# IRIS1304_v3_0.net
KiCad netlist of a schematic drawn in EAGLE
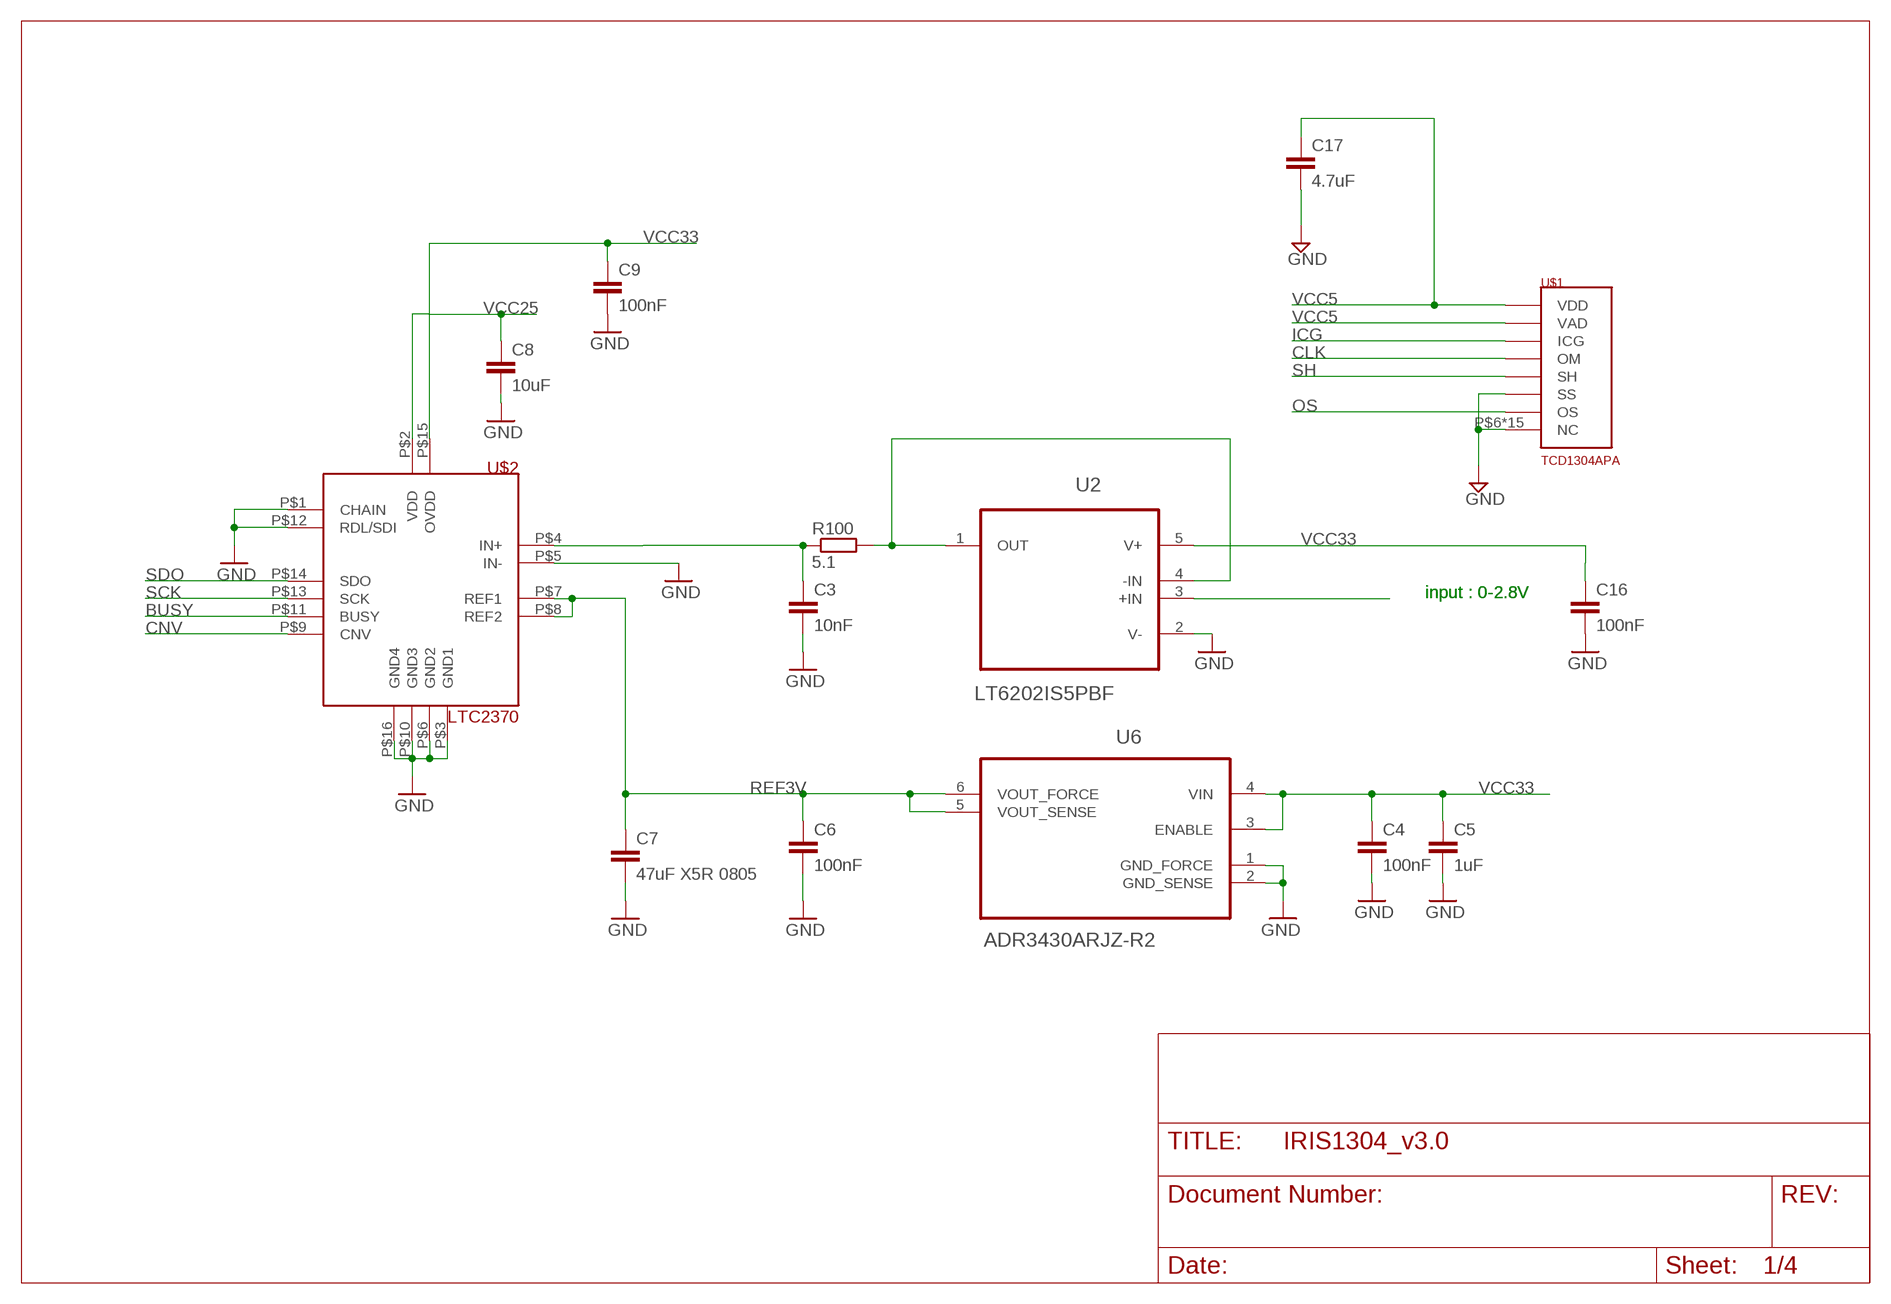
[diagram p0: schematic, sheet 1]
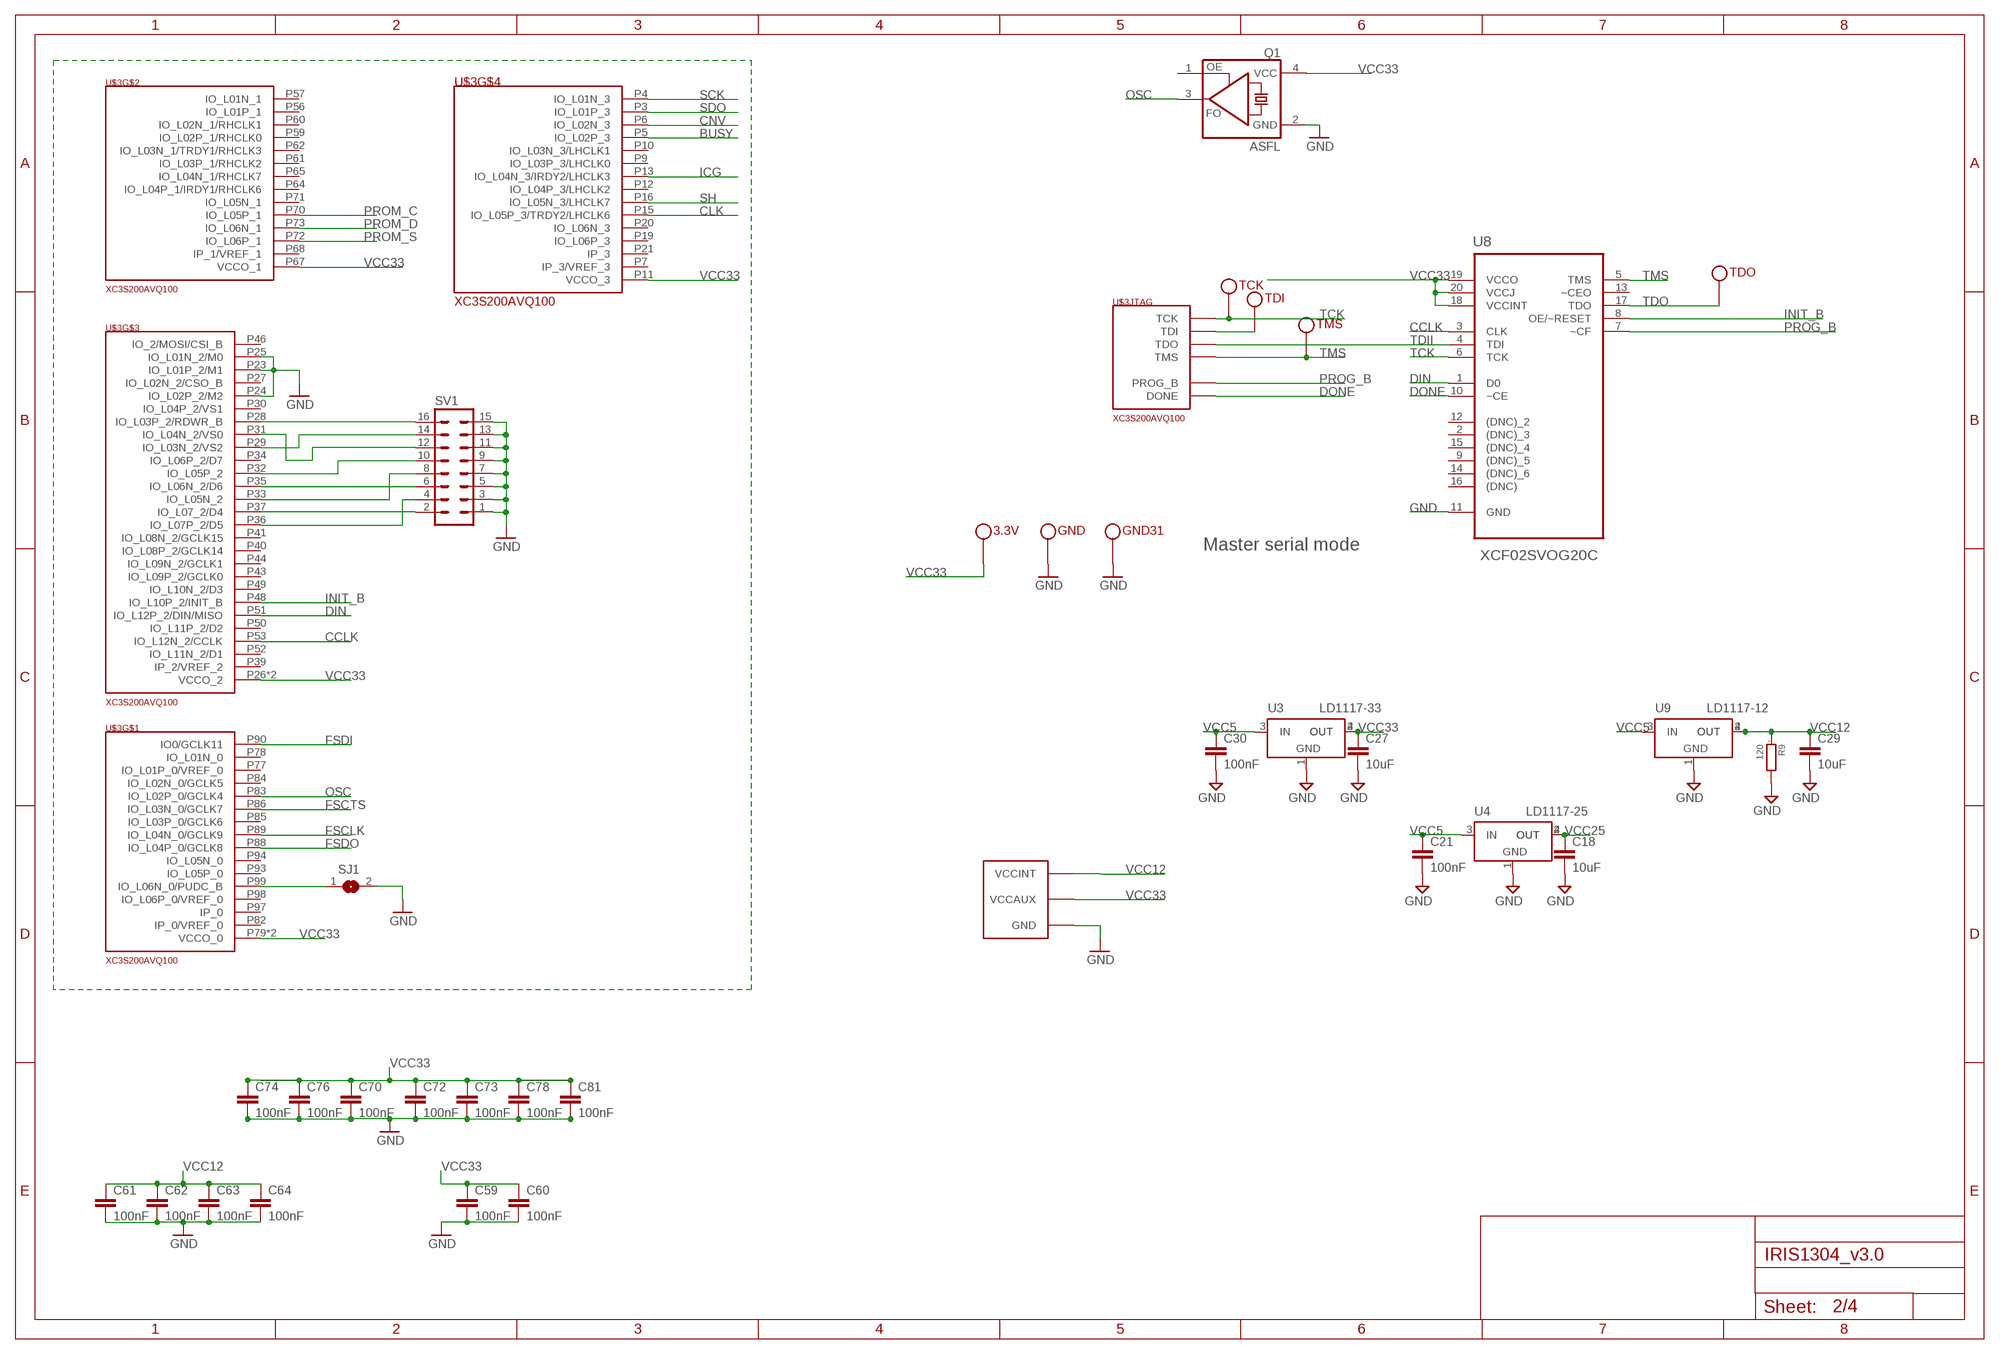
[diagram p1: schematic, sheet 2]
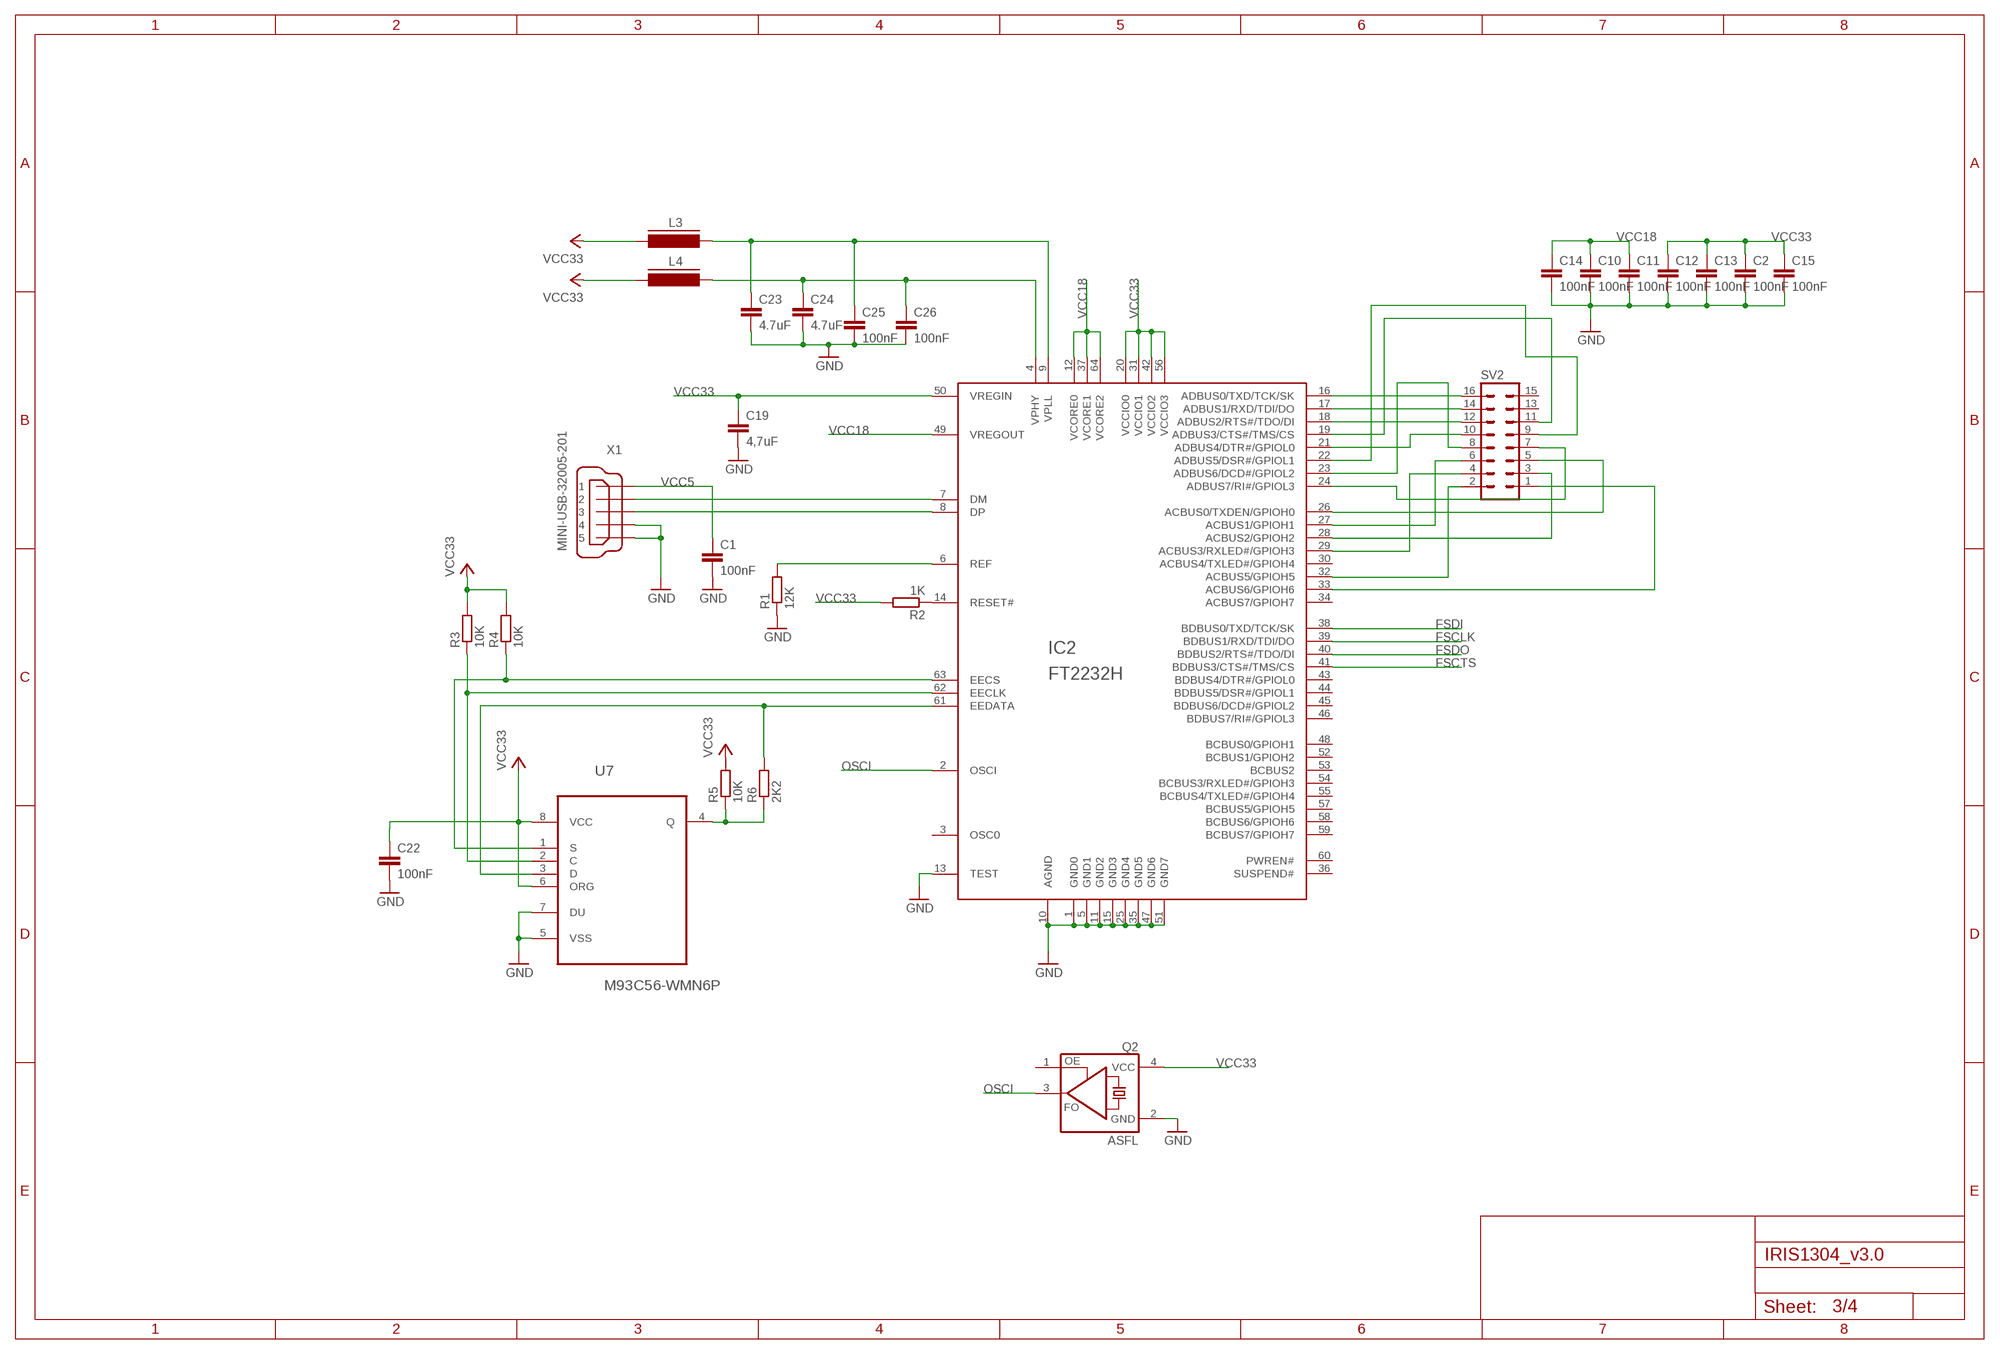
[diagram p2: schematic, sheet 3]
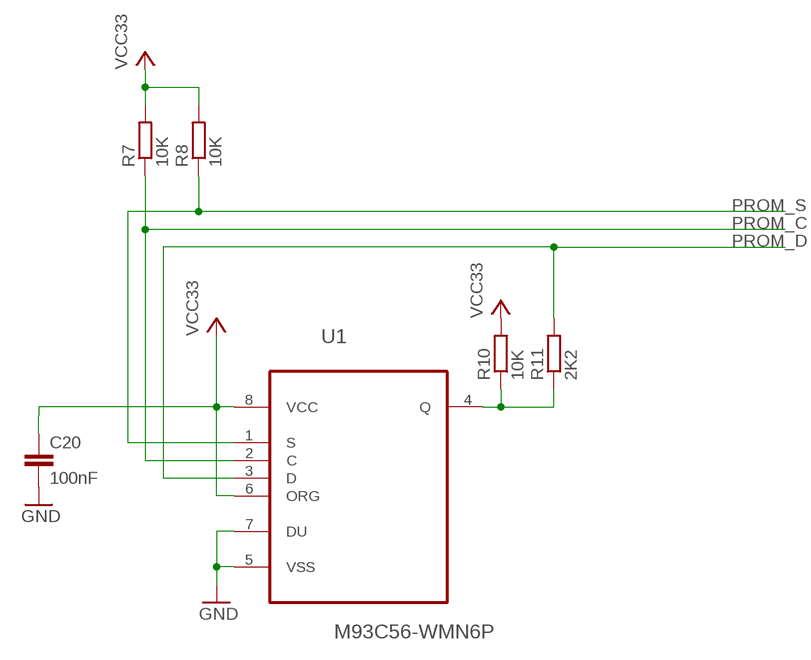
[diagram p3: schematic, sheet 4]

(export (version "E")
  (design (tool "Eeschema 10.0.6"))
  (components
    (comp (ref "C1")
      (value "100nF")
      (footprint "eagle-import:C0603")
      (fields (field (name "MF") "AVX") (field (name "MPN") "06033G104ZAT2A"))
      (libsource (lib "eagle-import") (part "C-EUC0603"))
    )
    (comp (ref "C2")
      (value "100nF")
      (footprint "eagle-import:C0603")
      (fields (field (name "MF") "AVX") (field (name "MPN") "06033G104ZAT2A"))
      (libsource (lib "eagle-import") (part "C-EUC0603"))
    )
    (comp (ref "C10")
      (value "100nF")
      (footprint "eagle-import:C0603")
      (fields (field (name "MF") "AVX") (field (name "MPN") "06033G104ZAT2A"))
      (libsource (lib "eagle-import") (part "C-EUC0603"))
    )
    (comp (ref "C11")
      (value "100nF")
      (footprint "eagle-import:C0603")
      (fields (field (name "MF") "AVX") (field (name "MPN") "06033G104ZAT2A"))
      (libsource (lib "eagle-import") (part "C-EUC0603"))
    )
    (comp (ref "C12")
      (value "100nF")
      (footprint "eagle-import:C0603")
      (fields (field (name "MF") "AVX") (field (name "MPN") "06033G104ZAT2A"))
      (libsource (lib "eagle-import") (part "C-EUC0603"))
    )
    (comp (ref "C13")
      (value "100nF")
      (footprint "eagle-import:C0603")
      (fields (field (name "MF") "AVX") (field (name "MPN") "06033G104ZAT2A"))
      (libsource (lib "eagle-import") (part "C-EUC0603"))
    )
    (comp (ref "C14")
      (value "100nF")
      (footprint "eagle-import:C0603")
      (fields (field (name "MF") "AVX") (field (name "MPN") "06033G104ZAT2A"))
      (libsource (lib "eagle-import") (part "C-EUC0603"))
    )
    (comp (ref "C15")
      (value "100nF")
      (footprint "eagle-import:C0603")
      (fields (field (name "MF") "AVX") (field (name "MPN") "06033G104ZAT2A"))
      (libsource (lib "eagle-import") (part "C-EUC0603"))
    )
    (comp (ref "C19")
      (value "4,7uF")
      (footprint "eagle-import:C0805")
      (fields (field (name "MF") "AVX") (field (name "MPN") "0805ZD335KAT2A"))
      (libsource (lib "eagle-import") (part "C-EUC0805"))
    )
    (comp (ref "C22")
      (value "100nF")
      (footprint "eagle-import:C0603")
      (fields (field (name "MF") "AVX") (field (name "MPN") "06033G104ZAT2A"))
      (libsource (lib "eagle-import") (part "C-EUC0603"))
    )
    (comp (ref "C23")
      (value "4.7uF")
      (footprint "eagle-import:C0603")
      (fields (field (name "MF") "YAGEO (PHYCOMP)") (field (name "MPN") "CC0603KRX5R6BB475"))
      (libsource (lib "eagle-import") (part "C-EUC0603"))
    )
    (comp (ref "C24")
      (value "4.7uF")
      (footprint "eagle-import:C0603")
      (fields (field (name "MF") "YAGEO (PHYCOMP)") (field (name "MPN") "CC0603KRX5R6BB475"))
      (libsource (lib "eagle-import") (part "C-EUC0603"))
    )
    (comp (ref "C25")
      (value "100nF")
      (footprint "eagle-import:C0603")
      (fields (field (name "MF") "AVX") (field (name "MPN") "06033G104ZAT2A"))
      (libsource (lib "eagle-import") (part "C-EUC0603"))
    )
    (comp (ref "C26")
      (value "100nF")
      (footprint "eagle-import:C0603")
      (fields (field (name "MF") "AVX") (field (name "MPN") "06033G104ZAT2A"))
      (libsource (lib "eagle-import") (part "C-EUC0603"))
    )
    (comp (ref "IC2")
      (value "FT2232H")
      (footprint "eagle-import:LQFP64")
      (fields (field (name "MF") "FTDI") (field (name "MPN") "FT2232HL-R"))
      (libsource (lib "eagle-import") (part "FT2232H"))
    )
    (comp (ref "L3")
      (value "FERRITE_BEAD805")
      (footprint "eagle-import:FB805")
      (libsource (lib "eagle-import") (part "FERRITE_BEAD805"))
    )
    (comp (ref "L4")
      (value "FERRITE_BEAD805")
      (footprint "eagle-import:FB805")
      (libsource (lib "eagle-import") (part "FERRITE_BEAD805"))
    )
    (comp (ref "Q2")
      (value "ASFL")
      (footprint "eagle-import:ASF")
      (fields
        (field (name "MPN") "ASFLM1-50.000MHZ-C-T")
        (field (name "MF") "ABRACON")
        (field (name "MPN_1") "ASFL1-12.000MHZ-EK-T")
        (field (name "OC_FARNELL") "7943088")
      )
      (libsource (lib "eagle-import") (part "ASFL"))
    )
    (comp (ref "R1")
      (value "12K")
      (footprint "eagle-import:R0603")
      (fields (field (name "MF") "TE CONNECTIVITY") (field (name "MPN") "CPF0201D12K1C1"))
      (libsource (lib "eagle-import") (part "R-EU_R0603"))
    )
    (comp (ref "R2")
      (value "1K")
      (footprint "eagle-import:R0603")
      (fields (field (name "MF") "VISHAY DRALORIC") (field (name "MPN") "CRCW06031K00FKEA"))
      (libsource (lib "eagle-import") (part "R-EU_R0603"))
    )
    (comp (ref "R3")
      (value "10K")
      (footprint "eagle-import:R0603")
      (fields (field (name "MF") "TE CONNECTIVITY / NEOHM") (field (name "MPN") "CPF0603F10KC1"))
      (libsource (lib "eagle-import") (part "R-EU_R0603"))
    )
    (comp (ref "R4")
      (value "10K")
      (footprint "eagle-import:R0603")
      (fields (field (name "MF") "TE CONNECTIVITY / NEOHM") (field (name "MPN") "CPF0603F10KC1"))
      (libsource (lib "eagle-import") (part "R-EU_R0603"))
    )
    (comp (ref "R5")
      (value "10K")
      (footprint "eagle-import:R0603")
      (fields (field (name "MF") "TE CONNECTIVITY / NEOHM") (field (name "MPN") "CPF0603F10KC1"))
      (libsource (lib "eagle-import") (part "R-EU_R0603"))
    )
    (comp (ref "R6")
      (value "2K2")
      (footprint "eagle-import:R0603")
      (fields (field (name "MF") "PANASONIC ELECTRONIC COMPONENTS") (field (name "MPN") "ERJP03F2201V"))
      (libsource (lib "eagle-import") (part "R-EU_R0603"))
    )
    (comp (ref "SV2")
      (value "ML16")
      (footprint "eagle-import:ML16")
      (libsource (lib "eagle-import") (part "ML16"))
    )
    (comp (ref "U7")
      (value "M93C56-WMN6P")
      (footprint "eagle-import:SOIC127P600X175-8N")
      (fields (field (name "MF") "STMICROELECTRONICS"))
      (libsource (lib "eagle-import") (part "M93C56-WMN6P"))
    )
    (comp (ref "X1")
      (value "MINI-USB-32005-201")
      (footprint "eagle-import:32005-201")
      (fields
        (field (name "MF") "WURTH ELEKTRONIK")
        (field (name "MPN") "65100516121")
        (field (name "OC_FARNELL") "1642036")
      )
      (libsource (lib "eagle-import") (part "MINI-USB-32005-201"))
    )
    (comp (ref "C20")
      (value "100nF")
      (footprint "eagle-import:C0603")
      (fields (field (name "MF") "AVX") (field (name "MPN") "06033G104ZAT2A"))
      (libsource (lib "eagle-import") (part "C-EUC0603"))
    )
    (comp (ref "R7")
      (value "10K")
      (footprint "eagle-import:R0603")
      (fields (field (name "MF") "TE CONNECTIVITY / NEOHM") (field (name "MPN") "CPF0603F10KC1"))
      (libsource (lib "eagle-import") (part "R-EU_R0603"))
    )
    (comp (ref "R8")
      (value "10K")
      (footprint "eagle-import:R0603")
      (fields (field (name "MF") "TE CONNECTIVITY / NEOHM") (field (name "MPN") "CPF0603F10KC1"))
      (libsource (lib "eagle-import") (part "R-EU_R0603"))
    )
    (comp (ref "R10")
      (value "10K")
      (footprint "eagle-import:R0603")
      (fields (field (name "MF") "TE CONNECTIVITY / NEOHM") (field (name "MPN") "CPF0603F10KC1"))
      (libsource (lib "eagle-import") (part "R-EU_R0603"))
    )
    (comp (ref "R11")
      (value "2K2")
      (footprint "eagle-import:R0603")
      (fields (field (name "MF") "PANASONIC ELECTRONIC COMPONENTS") (field (name "MPN") "ERJP03F2201V"))
      (libsource (lib "eagle-import") (part "R-EU_R0603"))
    )
    (comp (ref "U1")
      (value "M93C56-WMN6P")
      (footprint "eagle-import:SOIC127P600X175-8N")
      (fields (field (name "MF") "STMICROELECTRONICS"))
      (libsource (lib "eagle-import") (part "M93C56-WMN6P"))
    )
    (comp (ref "3.3V")
      (value "TEST")
      (footprint "eagle-import:TEST")
      (fields (field (name "MF") "ITT CANNON") (field (name "MPN") "001-1007-040FB9"))
      (libsource (lib "eagle-import") (part "TEST"))
    )
    (comp (ref "C18")
      (value "10uF")
      (footprint "eagle-import:C0603")
      (fields (field (name "MF") "KEMET") (field (name "MPN") "C0603C106M9PACTU"))
      (libsource (lib "eagle-import") (part "C-EUC0603"))
    )
    (comp (ref "C21")
      (value "100nF")
      (footprint "eagle-import:C0603")
      (fields (field (name "MF") "AVX") (field (name "MPN") "06033G104ZAT2A"))
      (libsource (lib "eagle-import") (part "C-EUC0603"))
    )
    (comp (ref "C27")
      (value "10uF")
      (footprint "eagle-import:C0603")
      (fields (field (name "MF") "KEMET") (field (name "MPN") "C0603C106M9PACTU"))
      (libsource (lib "eagle-import") (part "C-EUC0603"))
    )
    (comp (ref "C29")
      (value "10uF")
      (footprint "eagle-import:C0603")
      (fields (field (name "MF") "KEMET") (field (name "MPN") "C0603C106M9PACTU"))
      (libsource (lib "eagle-import") (part "C-EUC0603"))
    )
    (comp (ref "C30")
      (value "100nF")
      (footprint "eagle-import:C0603")
      (fields (field (name "MF") "AVX") (field (name "MPN") "06033G104ZAT2A"))
      (libsource (lib "eagle-import") (part "C-EUC0603"))
    )
    (comp (ref "C59")
      (value "100nF")
      (footprint "eagle-import:C0603")
      (fields (field (name "MF") "AVX") (field (name "MPN") "06033G104ZAT2A"))
      (libsource (lib "eagle-import") (part "C-EUC0603"))
    )
    (comp (ref "C60")
      (value "100nF")
      (footprint "eagle-import:C0603")
      (fields (field (name "MF") "AVX") (field (name "MPN") "06033G104ZAT2A"))
      (libsource (lib "eagle-import") (part "C-EUC0603"))
    )
    (comp (ref "C61")
      (value "100nF")
      (footprint "eagle-import:C0603")
      (fields (field (name "MF") "AVX") (field (name "MPN") "06033G104ZAT2A"))
      (libsource (lib "eagle-import") (part "C-EUC0603"))
    )
    (comp (ref "C62")
      (value "100nF")
      (footprint "eagle-import:C0603")
      (fields (field (name "MF") "AVX") (field (name "MPN") "06033G104ZAT2A"))
      (libsource (lib "eagle-import") (part "C-EUC0603"))
    )
    (comp (ref "C63")
      (value "100nF")
      (footprint "eagle-import:C0603")
      (fields (field (name "MF") "AVX") (field (name "MPN") "06033G104ZAT2A"))
      (libsource (lib "eagle-import") (part "C-EUC0603"))
    )
    (comp (ref "C64")
      (value "100nF")
      (footprint "eagle-import:C0603")
      (fields (field (name "MF") "AVX") (field (name "MPN") "06033G104ZAT2A"))
      (libsource (lib "eagle-import") (part "C-EUC0603"))
    )
    (comp (ref "C70")
      (value "100nF")
      (footprint "eagle-import:C0603")
      (fields (field (name "MF") "AVX") (field (name "MPN") "06033G104ZAT2A"))
      (libsource (lib "eagle-import") (part "C-EUC0603"))
    )
    (comp (ref "C72")
      (value "100nF")
      (footprint "eagle-import:C0603")
      (fields (field (name "MF") "AVX") (field (name "MPN") "06033G104ZAT2A"))
      (libsource (lib "eagle-import") (part "C-EUC0603"))
    )
    (comp (ref "C73")
      (value "100nF")
      (footprint "eagle-import:C0603")
      (fields (field (name "MF") "AVX") (field (name "MPN") "06033G104ZAT2A"))
      (libsource (lib "eagle-import") (part "C-EUC0603"))
    )
    (comp (ref "C74")
      (value "100nF")
      (footprint "eagle-import:C0603")
      (fields (field (name "MF") "AVX") (field (name "MPN") "06033G104ZAT2A"))
      (libsource (lib "eagle-import") (part "C-EUC0603"))
    )
    (comp (ref "C76")
      (value "100nF")
      (footprint "eagle-import:C0603")
      (fields (field (name "MF") "AVX") (field (name "MPN") "06033G104ZAT2A"))
      (libsource (lib "eagle-import") (part "C-EUC0603"))
    )
    (comp (ref "C78")
      (value "100nF")
      (footprint "eagle-import:C0603")
      (fields (field (name "MF") "AVX") (field (name "MPN") "06033G104ZAT2A"))
      (libsource (lib "eagle-import") (part "C-EUC0603"))
    )
    (comp (ref "C81")
      (value "100nF")
      (footprint "eagle-import:C0603")
      (fields (field (name "MF") "AVX") (field (name "MPN") "06033G104ZAT2A"))
      (libsource (lib "eagle-import") (part "C-EUC0603"))
    )
    (comp (ref "GND")
      (value "TEST")
      (footprint "eagle-import:TEST")
      (fields (field (name "MF") "ITT CANNON") (field (name "MPN") "001-1007-040FB9"))
      (libsource (lib "eagle-import") (part "TEST"))
    )
    (comp (ref "GND31")
      (value "TEST")
      (footprint "eagle-import:TEST")
      (fields (field (name "MF") "ITT CANNON") (field (name "MPN") "001-1007-040FB9"))
      (libsource (lib "eagle-import") (part "TEST"))
    )
    (comp (ref "Q1")
      (value "ASFL")
      (footprint "eagle-import:ASF")
      (fields
        (field (name "MPN") "ASFLM1-50.000MHZ-C-T")
        (field (name "MF") "ABRACON")
        (field (name "MPN_1") "ASFL1-12.000MHZ-EK-T")
        (field (name "OC_FARNELL") "7943088")
      )
      (libsource (lib "eagle-import") (part "ASFL"))
    )
    (comp (ref "R9")
      (value "120")
      (footprint "eagle-import:0805@1")
      (fields (field (name "MF") "TE CONNECTIVITY / SIGMA INDUCTORS") (field (name "MPN") "BMB2A0120AN1"))
      (libsource (lib "eagle-import") (part "R0805"))
    )
    (comp (ref "SJ1") (value "SJ") (footprint "eagle-import:SJ") (libsource (lib "eagle-import") (part "SJ")))
    (comp (ref "SV1")
      (value "ML16")
      (footprint "eagle-import:ML16")
      (libsource (lib "eagle-import") (part "ML16"))
    )
    (comp (ref "TCK")
      (value "TEST")
      (footprint "eagle-import:TEST")
      (fields (field (name "MF") "ITT CANNON") (field (name "MPN") "001-1007-040FB9"))
      (libsource (lib "eagle-import") (part "TEST"))
    )
    (comp (ref "TDI")
      (value "TEST")
      (footprint "eagle-import:TEST")
      (fields (field (name "MF") "ITT CANNON") (field (name "MPN") "001-1007-040FB9"))
      (libsource (lib "eagle-import") (part "TEST"))
    )
    (comp (ref "TDO")
      (value "TEST")
      (footprint "eagle-import:TEST")
      (fields (field (name "MF") "ITT CANNON") (field (name "MPN") "001-1007-040FB9"))
      (libsource (lib "eagle-import") (part "TEST"))
    )
    (comp (ref "TMS")
      (value "TEST")
      (footprint "eagle-import:TEST")
      (fields (field (name "MF") "ITT CANNON") (field (name "MPN") "001-1007-040FB9"))
      (libsource (lib "eagle-import") (part "TEST"))
    )
    (comp (ref "U$3")
      (value "XC3S200AVQ100")
      (footprint "eagle-import:VQ100")
      (fields
        (field (name "MF") "XILINX")
        (field (name "MPN") "XC3S200A-4VQG100C")
        (field (name "OC_FARNELL") "1876204")
      )
      (libsource (lib "eagle-import") (part "XC3S200AVQ100"))
    )
    (comp (ref "U3")
      (value "LD1117-33")
      (footprint "eagle-import:SOT223")
      (fields (field (name "MF") "LINEAR TECHNOLOGY") (field (name "MPN") "LT1117CST-3.3#PBF"))
      (libsource (lib "eagle-import") (part "LD1117"))
    )
    (comp (ref "U4")
      (value "LD1117-25")
      (footprint "eagle-import:SOT223")
      (fields (field (name "MF") "STMICROELECTRONICS") (field (name "MPN") "LD1117S25TR"))
      (libsource (lib "eagle-import") (part "LD1117"))
    )
    (comp (ref "U8")
      (value "XCF02SVOG20C")
      (footprint "eagle-import:SOP65P640X119-20N")
      (fields (field (name "MF") "XILINX"))
      (libsource (lib "eagle-import") (part "XCF02SVOG20C"))
    )
    (comp (ref "U9")
      (value "LD1117-12")
      (footprint "eagle-import:SOT223")
      (fields (field (name "MF") "LINEAR TECHNOLOGY") (field (name "MPN") "LT1117IST#PBF"))
      (libsource (lib "eagle-import") (part "LD1117"))
    )
    (comp (ref "C3")
      (value "10nF")
      (footprint "eagle-import:C0603")
      (fields (field (name "MF") "AVX") (field (name "MPN") "06035G103ZAT2A"))
      (libsource (lib "eagle-import") (part "C-EUC0603"))
    )
    (comp (ref "C4")
      (value "100nF")
      (footprint "eagle-import:C0603")
      (fields (field (name "MF") "AVX") (field (name "MPN") "06033G104ZAT2A"))
      (libsource (lib "eagle-import") (part "C-EUC0603"))
    )
    (comp (ref "C5")
      (value "1uF")
      (footprint "eagle-import:C0603")
      (fields (field (name "MF") "KEMET") (field (name "MPN") "C0603C105K3PACTU"))
      (libsource (lib "eagle-import") (part "C-EUC0603"))
    )
    (comp (ref "C6")
      (value "100nF")
      (footprint "eagle-import:C0603")
      (fields (field (name "MF") "AVX") (field (name "MPN") "06033G104ZAT2A"))
      (libsource (lib "eagle-import") (part "C-EUC0603"))
    )
    (comp (ref "C7")
      (value "47uF X5R 0805")
      (footprint "eagle-import:C0805")
      (fields (field (name "MF") "KEMET") (field (name "MPN") "C0805C476M9PACTU"))
      (libsource (lib "eagle-import") (part "C-EUC0805"))
    )
    (comp (ref "C8")
      (value "10uF")
      (footprint "eagle-import:C0603")
      (fields (field (name "MF") "KEMET") (field (name "MPN") "C0603C106M9PACTU"))
      (libsource (lib "eagle-import") (part "C-EUC0603"))
    )
    (comp (ref "C9")
      (value "100nF")
      (footprint "eagle-import:C0603")
      (fields (field (name "MF") "AVX") (field (name "MPN") "06033G104ZAT2A"))
      (libsource (lib "eagle-import") (part "C-EUC0603"))
    )
    (comp (ref "C16")
      (value "100nF")
      (footprint "eagle-import:C0603")
      (fields (field (name "MF") "AVX") (field (name "MPN") "06033G104ZAT2A"))
      (libsource (lib "eagle-import") (part "C-EUC0603"))
    )
    (comp (ref "C17")
      (value "4.7uF")
      (footprint "eagle-import:C0603")
      (fields (field (name "MF") "YAGEO (PHYCOMP)") (field (name "MPN") "CC0603KRX5R6BB475"))
      (libsource (lib "eagle-import") (part "C-EUC0603"))
    )
    (comp (ref "R100")
      (value "5.1")
      (footprint "eagle-import:R0603")
      (fields (field (name "MF") "VISHAY DALE") (field (name "MPN") "CRCW06035R10FNEA"))
      (libsource (lib "eagle-import") (part "R-EU_R0603"))
    )
    (comp (ref "U$1")
      (value "TCD1304APA")
      (footprint "eagle-import:ILX511")
      (libsource (lib "eagle-import") (part "TCD1304APA"))
    )
    (comp (ref "U$2")
      (value "LTC2370")
      (footprint "eagle-import:MSOP-16")
      (fields (field (name "MF") "LINEAR TECHNOLOGY") (field (name "MPN") "LTC2370CMS-16"))
      (libsource (lib "eagle-import") (part "LTC2370"))
    )
    (comp (ref "U2")
      (value "LT6202IS5PBF")
      (footprint "eagle-import:SOT95P280X100-5N")
      (fields (field (name "MPN") "LT6202IS5#PBF") (field (name "MF") "LINEAR TECHNOLOGY"))
      (libsource (lib "eagle-import") (part "LT6202IS5PBF"))
    )
    (comp (ref "U6")
      (value "ADR3430ARJZ-R2")
      (footprint "eagle-import:SOT95P280X145-6N")
      (fields (field (name "MF") "ANALOG DEVICES"))
      (libsource (lib "eagle-import") (part "ADR3430ARJZ-R2"))
    )
  )
  (nets
    (net (code "1") (name "BUSY") (class "Default")
      (node (ref "U$2") (pin "P$11") (pinfunction "BUSY_P$11") (pintype "bidirectional"))
      (node (ref "U$3") (pin "P5") (pinfunction "IO_L02P_3_P5") (pintype "bidirectional"))
    )
    (net (code "2") (name "CCLK") (class "Default")
      (node (ref "U$3") (pin "P53") (pinfunction "IO_L12N_2/CCLK_P53") (pintype "bidirectional"))
      (node (ref "U8") (pin "3") (pinfunction "CLK_3") (pintype "input"))
    )
    (net (code "3") (name "CLK") (class "Default")
      (node (ref "U$1") (pin "P$4") (pinfunction "OM_P$4") (pintype "bidirectional"))
      (node (ref "U$3") (pin "P15") (pinfunction "IO_L05P_3/TRDY2/LHCLK6_P15") (pintype "bidirectional"))
    )
    (net (code "4") (name "CNV") (class "Default")
      (node (ref "U$2") (pin "P$9") (pinfunction "CNV_P$9") (pintype "bidirectional"))
      (node (ref "U$3") (pin "P6") (pinfunction "IO_L02N_3_P6") (pintype "bidirectional"))
    )
    (net (code "5") (name "DIN") (class "Default")
      (node (ref "U$3") (pin "P51") (pinfunction "IO_L12P_2/DIN/MISO_P51") (pintype "bidirectional"))
      (node (ref "U8") (pin "1") (pinfunction "D0_1") (pintype "input"))
    )
    (net (code "6") (name "DONE") (class "Default")
      (node (ref "U$3") (pin "P54") (pinfunction "DONE_P54") (pintype "bidirectional"))
      (node (ref "U8") (pin "10") (pinfunction "~{CE}_10") (pintype "input"))
    )
    (net (code "7") (name "FSCLK") (class "Default")
      (node (ref "IC2") (pin "39") (pinfunction "BDBUS1/RXD/TDI/DO_39") (pintype "bidirectional"))
      (node (ref "U$3") (pin "P89") (pinfunction "IO_L04N_0/GCLK9_P89") (pintype "bidirectional"))
    )
    (net (code "8") (name "FSCTS") (class "Default")
      (node (ref "IC2") (pin "41") (pinfunction "BDBUS3/CTS#/TMS/CS_41") (pintype "bidirectional"))
      (node (ref "U$3") (pin "P86") (pinfunction "IO_L03N_0/GCLK7_P86") (pintype "bidirectional"))
    )
    (net (code "9") (name "FSDI") (class "Default")
      (node (ref "IC2") (pin "38") (pinfunction "BDBUS0/TXD/TCK/SK_38") (pintype "bidirectional"))
      (node (ref "U$3") (pin "P90") (pinfunction "IO0/GCLK11_P90") (pintype "bidirectional"))
    )
    (net (code "10") (name "FSDO") (class "Default")
      (node (ref "IC2") (pin "40") (pinfunction "BDBUS2/RTS#/TDO/DI_40") (pintype "bidirectional"))
      (node (ref "U$3") (pin "P88") (pinfunction "IO_L04P_0/GCLK8_P88") (pintype "bidirectional"))
    )
    (net (code "11") (name "GND") (class "Default")
      (node (ref "C1") (pin "2") (pinfunction "2_2") (pintype "passive"))
      (node (ref "C10") (pin "2") (pinfunction "2_2") (pintype "passive"))
      (node (ref "C11") (pin "2") (pinfunction "2_2") (pintype "passive"))
      (node (ref "C12") (pin "2") (pinfunction "2_2") (pintype "passive"))
      (node (ref "C13") (pin "2") (pinfunction "2_2") (pintype "passive"))
      (node (ref "C14") (pin "2") (pinfunction "2_2") (pintype "passive"))
      (node (ref "C15") (pin "2") (pinfunction "2_2") (pintype "passive"))
      (node (ref "C16") (pin "2") (pinfunction "2_2") (pintype "passive"))
      (node (ref "C17") (pin "2") (pinfunction "2_2") (pintype "passive"))
      (node (ref "C18") (pin "2") (pinfunction "2_2") (pintype "passive"))
      (node (ref "C19") (pin "2") (pinfunction "2_2") (pintype "passive"))
      (node (ref "C2") (pin "2") (pinfunction "2_2") (pintype "passive"))
      (node (ref "C20") (pin "2") (pinfunction "2_2") (pintype "passive"))
      (node (ref "C21") (pin "2") (pinfunction "2_2") (pintype "passive"))
      (node (ref "C22") (pin "2") (pinfunction "2_2") (pintype "passive"))
      (node (ref "C23") (pin "2") (pinfunction "2_2") (pintype "passive"))
      (node (ref "C24") (pin "2") (pinfunction "2_2") (pintype "passive"))
      (node (ref "C25") (pin "2") (pinfunction "2_2") (pintype "passive"))
      (node (ref "C26") (pin "2") (pinfunction "2_2") (pintype "passive"))
      (node (ref "C27") (pin "2") (pinfunction "2_2") (pintype "passive"))
      (node (ref "C29") (pin "2") (pinfunction "2_2") (pintype "passive"))
      (node (ref "C3") (pin "2") (pinfunction "2_2") (pintype "passive"))
      (node (ref "C30") (pin "2") (pinfunction "2_2") (pintype "passive"))
      (node (ref "C4") (pin "2") (pinfunction "2_2") (pintype "passive"))
      (node (ref "C5") (pin "2") (pinfunction "2_2") (pintype "passive"))
      (node (ref "C59") (pin "2") (pinfunction "2_2") (pintype "passive"))
      (node (ref "C6") (pin "2") (pinfunction "2_2") (pintype "passive"))
      (node (ref "C60") (pin "2") (pinfunction "2_2") (pintype "passive"))
      (node (ref "C61") (pin "2") (pinfunction "2_2") (pintype "passive"))
      (node (ref "C62") (pin "2") (pinfunction "2_2") (pintype "passive"))
      (node (ref "C63") (pin "2") (pinfunction "2_2") (pintype "passive"))
      (node (ref "C64") (pin "2") (pinfunction "2_2") (pintype "passive"))
      (node (ref "C7") (pin "2") (pinfunction "2_2") (pintype "passive"))
      (node (ref "C70") (pin "2") (pinfunction "2_2") (pintype "passive"))
      (node (ref "C72") (pin "2") (pinfunction "2_2") (pintype "passive"))
      (node (ref "C73") (pin "2") (pinfunction "2_2") (pintype "passive"))
      (node (ref "C74") (pin "2") (pinfunction "2_2") (pintype "passive"))
      (node (ref "C76") (pin "2") (pinfunction "2_2") (pintype "passive"))
      (node (ref "C78") (pin "2") (pinfunction "2_2") (pintype "passive"))
      (node (ref "C8") (pin "2") (pinfunction "2_2") (pintype "passive"))
      (node (ref "C81") (pin "2") (pinfunction "2_2") (pintype "passive"))
      (node (ref "C9") (pin "2") (pinfunction "2_2") (pintype "passive"))
      (node (ref "GND") (pin "P$1") (pinfunction "P$1_P$1") (pintype "bidirectional"))
      (node (ref "GND31") (pin "P$1") (pinfunction "P$1_P$1") (pintype "bidirectional"))
      (node (ref "IC2") (pin "1") (pinfunction "GND0_1") (pintype "bidirectional"))
      (node (ref "IC2") (pin "10") (pinfunction "AGND_10") (pintype "bidirectional"))
      (node (ref "IC2") (pin "11") (pinfunction "GND2_11") (pintype "bidirectional"))
      (node (ref "IC2") (pin "13") (pinfunction "TEST_13") (pintype "bidirectional"))
      (node (ref "IC2") (pin "15") (pinfunction "GND3_15") (pintype "bidirectional"))
      (node (ref "IC2") (pin "25") (pinfunction "GND4_25") (pintype "bidirectional"))
      (node (ref "IC2") (pin "35") (pinfunction "GND5_35") (pintype "bidirectional"))
      (node (ref "IC2") (pin "47") (pinfunction "GND6_47") (pintype "bidirectional"))
      (node (ref "IC2") (pin "5") (pinfunction "GND1_5") (pintype "bidirectional"))
      (node (ref "IC2") (pin "51") (pinfunction "GND7_51") (pintype "bidirectional"))
      (node (ref "Q1") (pin "2") (pinfunction "GND_2") (pintype "power_in"))
      (node (ref "Q2") (pin "2") (pinfunction "GND_2") (pintype "power_in"))
      (node (ref "R1") (pin "1") (pinfunction "1_1") (pintype "passive"))
      (node (ref "R9") (pin "2") (pinfunction "2_2") (pintype "passive"))
      (node (ref "SJ1") (pin "2") (pinfunction "2_2") (pintype "passive"))
      (node (ref "SV1") (pin "1") (pinfunction "1_1") (pintype "passive"))
      (node (ref "SV1") (pin "11") (pinfunction "11_11") (pintype "passive"))
      (node (ref "SV1") (pin "13") (pinfunction "13_13") (pintype "passive"))
      (node (ref "SV1") (pin "15") (pinfunction "15_15") (pintype "passive"))
      (node (ref "SV1") (pin "3") (pinfunction "3_3") (pintype "passive"))
      (node (ref "SV1") (pin "5") (pinfunction "5_5") (pintype "passive"))
      (node (ref "SV1") (pin "7") (pinfunction "7_7") (pintype "passive"))
      (node (ref "SV1") (pin "9") (pinfunction "9_9") (pintype "passive"))
      (node (ref "U$1") (pin "P$10") (pinfunction "NC_P$10") (pintype "bidirectional"))
      (node (ref "U$1") (pin "P$11") (pinfunction "NC_P$11") (pintype "bidirectional"))
      (node (ref "U$1") (pin "P$12") (pinfunction "NC_P$12") (pintype "bidirectional"))
      (node (ref "U$1") (pin "P$13") (pinfunction "NC_P$13") (pintype "bidirectional"))
      (node (ref "U$1") (pin "P$14") (pinfunction "NC_P$14") (pintype "bidirectional"))
      (node (ref "U$1") (pin "P$15") (pinfunction "NC_P$15") (pintype "bidirectional"))
      (node (ref "U$1") (pin "P$16") (pinfunction "NC_P$16") (pintype "bidirectional"))
      (node (ref "U$1") (pin "P$17") (pinfunction "NC_P$17") (pintype "bidirectional"))
      (node (ref "U$1") (pin "P$18") (pinfunction "NC_P$18") (pintype "bidirectional"))
      (node (ref "U$1") (pin "P$19") (pinfunction "NC_P$19") (pintype "bidirectional"))
      (node (ref "U$1") (pin "P$20") (pinfunction "NC_P$20") (pintype "bidirectional"))
      (node (ref "U$1") (pin "P$22") (pinfunction "SS_P$22") (pintype "bidirectional"))
      (node (ref "U$1") (pin "P$6") (pinfunction "NC_P$6") (pintype "bidirectional"))
      (node (ref "U$1") (pin "P$7") (pinfunction "NC_P$7") (pintype "bidirectional"))
      (node (ref "U$1") (pin "P$8") (pinfunction "NC_P$8") (pintype "bidirectional"))
      (node (ref "U$1") (pin "P$9") (pinfunction "NC_P$9") (pintype "bidirectional"))
      (node (ref "U$2") (pin "P$1") (pinfunction "CHAIN_P$1") (pintype "bidirectional"))
      (node (ref "U$2") (pin "P$10") (pinfunction "GND3_P$10") (pintype "bidirectional"))
      (node (ref "U$2") (pin "P$12") (pinfunction "RDL/SDI_P$12") (pintype "bidirectional"))
      (node (ref "U$2") (pin "P$16") (pinfunction "GND4_P$16") (pintype "bidirectional"))
      (node (ref "U$2") (pin "P$3") (pinfunction "GND1_P$3") (pintype "bidirectional"))
      (node (ref "U$2") (pin "P$5") (pinfunction "IN-_P$5") (pintype "bidirectional"))
      (node (ref "U$2") (pin "P$6") (pinfunction "GND2_P$6") (pintype "bidirectional"))
      (node (ref "U$3") (pin "P14") (pinfunction "GND_P14") (pintype "bidirectional"))
      (node (ref "U$3") (pin "P18") (pinfunction "GND_P18") (pintype "bidirectional"))
      (node (ref "U$3") (pin "P23") (pinfunction "IO_L01P_2/M1_P23") (pintype "bidirectional"))
      (node (ref "U$3") (pin "P24") (pinfunction "IO_L02P_2/M2_P24") (pintype "bidirectional"))
      (node (ref "U$3") (pin "P25") (pinfunction "IO_L01N_2/M0_P25") (pintype "bidirectional"))
      (node (ref "U$3") (pin "P42") (pinfunction "GND_P42") (pintype "bidirectional"))
      (node (ref "U$3") (pin "P47") (pinfunction "GND_P47") (pintype "bidirectional"))
      (node (ref "U$3") (pin "P58") (pinfunction "GND_P58") (pintype "bidirectional"))
      (node (ref "U$3") (pin "P63") (pinfunction "GND_P63") (pintype "bidirectional"))
      (node (ref "U$3") (pin "P69") (pinfunction "GND_P69") (pintype "bidirectional"))
      (node (ref "U$3") (pin "P74") (pinfunction "GND_P74") (pintype "bidirectional"))
      (node (ref "U$3") (pin "P8") (pinfunction "GND_P8") (pintype "bidirectional"))
      (node (ref "U$3") (pin "P80") (pinfunction "GND_P80") (pintype "bidirectional"))
      (node (ref "U$3") (pin "P87") (pinfunction "GND_P87") (pintype "bidirectional"))
      (node (ref "U$3") (pin "P91") (pinfunction "GND_P91") (pintype "bidirectional"))
      (node (ref "U$3") (pin "P95") (pinfunction "GND_P95") (pintype "bidirectional"))
      (node (ref "U1") (pin "5") (pinfunction "VSS_5") (pintype "power_in"))
      (node (ref "U1") (pin "7") (pinfunction "DU_7") (pintype "input"))
      (node (ref "U2") (pin "2") (pinfunction "V-_2") (pintype "power_in"))
      (node (ref "U3") (pin "1") (pinfunction "GND_1") (pintype "power_in"))
      (node (ref "U4") (pin "1") (pinfunction "GND_1") (pintype "power_in"))
      (node (ref "U6") (pin "1") (pinfunction "GND_FORCE_1") (pintype "passive"))
      (node (ref "U6") (pin "2") (pinfunction "GND_SENSE_2") (pintype "passive"))
      (node (ref "U7") (pin "5") (pinfunction "VSS_5") (pintype "power_in"))
      (node (ref "U7") (pin "7") (pinfunction "DU_7") (pintype "input"))
      (node (ref "U8") (pin "11") (pinfunction "GND_11") (pintype "passive"))
      (node (ref "U9") (pin "1") (pinfunction "GND_1") (pintype "power_in"))
      (node (ref "X1") (pin "4") (pinfunction "4_4") (pintype "passive"))
      (node (ref "X1") (pin "5") (pinfunction "5_5") (pintype "passive"))
    )
    (net (code "12") (name "ICG") (class "Default")
      (node (ref "U$1") (pin "P$3") (pinfunction "ICG_P$3") (pintype "bidirectional"))
      (node (ref "U$3") (pin "P13") (pinfunction "IO_L04N_3/IRDY2/LHCLK3_P13") (pintype "bidirectional"))
    )
    (net (code "13") (name "INIT_B") (class "Default")
      (node (ref "U$3") (pin "P48") (pinfunction "IO_L10P_2/INIT_B_P48") (pintype "bidirectional"))
      (node (ref "U8") (pin "8") (pinfunction "OE/~{RESET}_8") (pintype "bidirectional"))
    )
    (net (code "14") (name "Net-(IC2-ACBUS0{slash}TXDEN{slash}GPIOH0)") (class "Default")
      (node (ref "IC2") (pin "26") (pinfunction "ACBUS0/TXDEN/GPIOH0_26") (pintype "bidirectional"))
      (node (ref "SV2") (pin "5") (pinfunction "5_5") (pintype "passive"))
    )
    (net (code "15") (name "Net-(IC2-ACBUS1{slash}GPIOH1)") (class "Default")
      (node (ref "IC2") (pin "27") (pinfunction "ACBUS1/GPIOH1_27") (pintype "bidirectional"))
      (node (ref "SV2") (pin "6") (pinfunction "6_6") (pintype "passive"))
    )
    (net (code "16") (name "Net-(IC2-ACBUS2{slash}GPIOH2)") (class "Default")
      (node (ref "IC2") (pin "28") (pinfunction "ACBUS2/GPIOH2_28") (pintype "bidirectional"))
      (node (ref "SV2") (pin "3") (pinfunction "3_3") (pintype "passive"))
    )
    (net (code "17") (name "Net-(IC2-ACBUS3{slash}RXLED#{slash}GPIOH3)") (class "Default")
      (node (ref "IC2") (pin "29") (pinfunction "ACBUS3/RXLED#/GPIOH3_29") (pintype "bidirectional"))
      (node (ref "SV2") (pin "4") (pinfunction "4_4") (pintype "passive"))
    )
    (net (code "18") (name "Net-(IC2-ACBUS5{slash}GPIOH5)") (class "Default")
      (node (ref "IC2") (pin "32") (pinfunction "ACBUS5/GPIOH5_32") (pintype "bidirectional"))
      (node (ref "SV2") (pin "2") (pinfunction "2_2") (pintype "passive"))
    )
    (net (code "19") (name "Net-(IC2-ACBUS6{slash}GPIOH6)") (class "Default")
      (node (ref "IC2") (pin "33") (pinfunction "ACBUS6/GPIOH6_33") (pintype "bidirectional"))
      (node (ref "SV2") (pin "1") (pinfunction "1_1") (pintype "passive"))
    )
    (net (code "20") (name "Net-(IC2-ADBUS0{slash}TXD{slash}TCK{slash}SK)") (class "Default")
      (node (ref "IC2") (pin "16") (pinfunction "ADBUS0/TXD/TCK/SK_16") (pintype "bidirectional"))
      (node (ref "SV2") (pin "16") (pinfunction "16_16") (pintype "passive"))
    )
    (net (code "21") (name "Net-(IC2-ADBUS1{slash}RXD{slash}TDI{slash}DO)") (class "Default")
      (node (ref "IC2") (pin "17") (pinfunction "ADBUS1/RXD/TDI/DO_17") (pintype "bidirectional"))
      (node (ref "SV2") (pin "14") (pinfunction "14_14") (pintype "passive"))
    )
    (net (code "22") (name "Net-(IC2-ADBUS2{slash}RTS#{slash}TDO{slash}DI)") (class "Default")
      (node (ref "IC2") (pin "18") (pinfunction "ADBUS2/RTS#/TDO/DI_18") (pintype "bidirectional"))
      (node (ref "SV2") (pin "12") (pinfunction "12_12") (pintype "passive"))
    )
    (net (code "23") (name "Net-(IC2-ADBUS3{slash}CTS#{slash}TMS{slash}CS)") (class "Default")
      (node (ref "IC2") (pin "19") (pinfunction "ADBUS3/CTS#/TMS/CS_19") (pintype "bidirectional"))
      (node (ref "SV2") (pin "11") (pinfunction "11_11") (pintype "passive"))
    )
    (net (code "24") (name "Net-(IC2-ADBUS4{slash}DTR#{slash}GPIOL0)") (class "Default")
      (node (ref "IC2") (pin "21") (pinfunction "ADBUS4/DTR#/GPIOL0_21") (pintype "bidirectional"))
      (node (ref "SV2") (pin "10") (pinfunction "10_10") (pintype "passive"))
    )
    (net (code "25") (name "Net-(IC2-ADBUS5{slash}DSR#{slash}GPIOL1)") (class "Default")
      (node (ref "IC2") (pin "22") (pinfunction "ADBUS5/DSR#/GPIOL1_22") (pintype "bidirectional"))
      (node (ref "SV2") (pin "9") (pinfunction "9_9") (pintype "passive"))
    )
    (net (code "26") (name "Net-(IC2-ADBUS6{slash}DCD#{slash}GPIOL2)") (class "Default")
      (node (ref "IC2") (pin "23") (pinfunction "ADBUS6/DCD#/GPIOL2_23") (pintype "bidirectional"))
      (node (ref "SV2") (pin "8") (pinfunction "8_8") (pintype "passive"))
    )
    (net (code "27") (name "Net-(IC2-ADBUS7{slash}RI#{slash}GPIOL3)") (class "Default")
      (node (ref "IC2") (pin "24") (pinfunction "ADBUS7/RI#/GPIOL3_24") (pintype "bidirectional"))
      (node (ref "SV2") (pin "7") (pinfunction "7_7") (pintype "passive"))
    )
    (net (code "28") (name "Net-(IC2-DM)") (class "Default")
      (node (ref "IC2") (pin "7") (pinfunction "DM_7") (pintype "bidirectional"))
      (node (ref "X1") (pin "2") (pinfunction "2_2") (pintype "passive"))
    )
    (net (code "29") (name "Net-(IC2-DP)") (class "Default")
      (node (ref "IC2") (pin "8") (pinfunction "DP_8") (pintype "bidirectional"))
      (node (ref "X1") (pin "3") (pinfunction "3_3") (pintype "passive"))
    )
    (net (code "30") (name "Net-(IC2-EECLK)") (class "Default")
      (node (ref "IC2") (pin "62") (pinfunction "EECLK_62") (pintype "bidirectional"))
      (node (ref "R3") (pin "1") (pinfunction "1_1") (pintype "passive"))
      (node (ref "U7") (pin "2") (pinfunction "C_2") (pintype "input"))
    )
    (net (code "31") (name "Net-(IC2-EECS)") (class "Default")
      (node (ref "IC2") (pin "63") (pinfunction "EECS_63") (pintype "bidirectional"))
      (node (ref "R4") (pin "1") (pinfunction "1_1") (pintype "passive"))
      (node (ref "U7") (pin "1") (pinfunction "S_1") (pintype "input"))
    )
    (net (code "32") (name "Net-(IC2-EEDATA)") (class "Default")
      (node (ref "IC2") (pin "61") (pinfunction "EEDATA_61") (pintype "bidirectional"))
      (node (ref "R6") (pin "2") (pinfunction "2_2") (pintype "passive"))
      (node (ref "U7") (pin "3") (pinfunction "D_3") (pintype "input"))
    )
    (net (code "33") (name "Net-(IC2-REF)") (class "Default")
      (node (ref "IC2") (pin "6") (pinfunction "REF_6") (pintype "bidirectional"))
      (node (ref "R1") (pin "2") (pinfunction "2_2") (pintype "passive"))
    )
    (net (code "34") (name "Net-(IC2-RESET#)") (class "Default")
      (node (ref "IC2") (pin "14") (pinfunction "RESET#_14") (pintype "bidirectional"))
      (node (ref "R2") (pin "1") (pinfunction "1_1") (pintype "passive"))
    )
    (net (code "35") (name "Net-(IC2-VPHY)") (class "Default")
      (node (ref "C24") (pin "1") (pinfunction "1_1") (pintype "passive"))
      (node (ref "C26") (pin "1") (pinfunction "1_1") (pintype "passive"))
      (node (ref "IC2") (pin "4") (pinfunction "VPHY_4") (pintype "bidirectional"))
      (node (ref "L4") (pin "1") (pinfunction "1_1") (pintype "passive"))
    )
    (net (code "36") (name "Net-(IC2-VPLL)") (class "Default")
      (node (ref "C23") (pin "1") (pinfunction "1_1") (pintype "passive"))
      (node (ref "C25") (pin "1") (pinfunction "1_1") (pintype "passive"))
      (node (ref "IC2") (pin "9") (pinfunction "VPLL_9") (pintype "bidirectional"))
      (node (ref "L3") (pin "1") (pinfunction "1_1") (pintype "passive"))
    )
    (net (code "37") (name "Net-(U$2-IN+)") (class "Default")
      (node (ref "C3") (pin "1") (pinfunction "1_1") (pintype "passive"))
      (node (ref "R100") (pin "1") (pinfunction "1_1") (pintype "passive"))
      (node (ref "U$2") (pin "P$4") (pinfunction "IN+_P$4") (pintype "bidirectional"))
    )
    (net (code "38") (name "Net-(U$3A-IO_L06N_0{slash}PUDC_B)") (class "Default")
      (node (ref "SJ1") (pin "1") (pinfunction "1_1") (pintype "passive"))
      (node (ref "U$3") (pin "P99") (pinfunction "IO_L06N_0/PUDC_B_P99") (pintype "bidirectional"))
    )
    (net (code "39") (name "Net-(U$3C-IO_L03N_2{slash}VS2)") (class "Default")
      (node (ref "SV1") (pin "14") (pinfunction "14_14") (pintype "passive"))
      (node (ref "U$3") (pin "P29") (pinfunction "IO_L03N_2/VS2_P29") (pintype "bidirectional"))
    )
    (net (code "40") (name "Net-(U$3C-IO_L03P_2{slash}RDWR_B)") (class "Default")
      (node (ref "SV1") (pin "16") (pinfunction "16_16") (pintype "passive"))
      (node (ref "U$3") (pin "P28") (pinfunction "IO_L03P_2/RDWR_B_P28") (pintype "bidirectional"))
    )
    (net (code "41") (name "Net-(U$3C-IO_L04N_2{slash}VS0)") (class "Default")
      (node (ref "SV1") (pin "12") (pinfunction "12_12") (pintype "passive"))
      (node (ref "U$3") (pin "P31") (pinfunction "IO_L04N_2/VS0_P31") (pintype "bidirectional"))
    )
    (net (code "42") (name "Net-(U$3C-IO_L05N_2)") (class "Default")
      (node (ref "SV1") (pin "8") (pinfunction "8_8") (pintype "passive"))
      (node (ref "U$3") (pin "P33") (pinfunction "IO_L05N_2_P33") (pintype "bidirectional"))
    )
    (net (code "43") (name "Net-(U$3C-IO_L05P_2)") (class "Default")
      (node (ref "SV1") (pin "10") (pinfunction "10_10") (pintype "passive"))
      (node (ref "U$3") (pin "P32") (pinfunction "IO_L05P_2_P32") (pintype "bidirectional"))
    )
    (net (code "44") (name "Net-(U$3C-IO_L06N_2{slash}D6)") (class "Default")
      (node (ref "SV1") (pin "6") (pinfunction "6_6") (pintype "passive"))
      (node (ref "U$3") (pin "P35") (pinfunction "IO_L06N_2/D6_P35") (pintype "bidirectional"))
    )
    (net (code "45") (name "Net-(U$3C-IO_L07P_2{slash}D5)") (class "Default")
      (node (ref "SV1") (pin "4") (pinfunction "4_4") (pintype "passive"))
      (node (ref "U$3") (pin "P36") (pinfunction "IO_L07P_2/D5_P36") (pintype "bidirectional"))
    )
    (net (code "46") (name "Net-(U$3C-IO_L07_2{slash}D4)") (class "Default")
      (node (ref "SV1") (pin "2") (pinfunction "2_2") (pintype "passive"))
      (node (ref "U$3") (pin "P37") (pinfunction "IO_L07_2/D4_P37") (pintype "bidirectional"))
    )
    (net (code "47") (name "Net-(U$3F-TDI)") (class "Default")
      (node (ref "TDI") (pin "P$1") (pinfunction "P$1_P$1") (pintype "bidirectional"))
      (node (ref "U$3") (pin "P2") (pinfunction "TDI_P2") (pintype "bidirectional"))
    )
    (net (code "48") (name "Net-(U1-Q)") (class "Default")
      (node (ref "R10") (pin "1") (pinfunction "1_1") (pintype "passive"))
      (node (ref "R11") (pin "1") (pinfunction "1_1") (pintype "passive"))
      (node (ref "U1") (pin "4") (pinfunction "Q_4") (pintype "output"))
    )
    (net (code "49") (name "Net-(U2--IN)") (class "Default")
      (node (ref "R100") (pin "2") (pinfunction "2_2") (pintype "passive"))
      (node (ref "U2") (pin "1") (pinfunction "OUT_1") (pintype "output"))
      (node (ref "U2") (pin "4") (pinfunction "-IN_4") (pintype "input"))
    )
    (net (code "50") (name "Net-(U7-Q)") (class "Default")
      (node (ref "R5") (pin "1") (pinfunction "1_1") (pintype "passive"))
      (node (ref "R6") (pin "1") (pinfunction "1_1") (pintype "passive"))
      (node (ref "U7") (pin "4") (pinfunction "Q_4") (pintype "output"))
    )
    (net (code "51") (name "OS") (class "Default")
      (node (ref "U$1") (pin "P$21") (pinfunction "OS_P$21") (pintype "bidirectional"))
      (node (ref "U2") (pin "3") (pinfunction "+IN_3") (pintype "input"))
    )
    (net (code "52") (name "OSC") (class "Default")
      (node (ref "Q1") (pin "3") (pinfunction "FO_3") (pintype "output"))
      (node (ref "U$3") (pin "P83") (pinfunction "IO_L02P_0/GCLK4_P83") (pintype "bidirectional"))
    )
    (net (code "53") (name "OSCI") (class "Default")
      (node (ref "IC2") (pin "2") (pinfunction "OSCI_2") (pintype "bidirectional"))
      (node (ref "Q2") (pin "3") (pinfunction "FO_3") (pintype "output"))
    )
    (net (code "54") (name "PROG_B") (class "Default")
      (node (ref "U$3") (pin "P100") (pinfunction "PROG_B_P100") (pintype "bidirectional"))
      (node (ref "U8") (pin "7") (pinfunction "~{CF}_7") (pintype "bidirectional"))
    )
    (net (code "55") (name "PROM_C") (class "Default")
      (node (ref "R7") (pin "1") (pinfunction "1_1") (pintype "passive"))
      (node (ref "U$3") (pin "P70") (pinfunction "IO_L05P_1_P70") (pintype "bidirectional"))
      (node (ref "U1") (pin "2") (pinfunction "C_2") (pintype "input"))
    )
    (net (code "56") (name "PROM_D") (class "Default")
      (node (ref "R11") (pin "2") (pinfunction "2_2") (pintype "passive"))
      (node (ref "U$3") (pin "P73") (pinfunction "IO_L06N_1_P73") (pintype "bidirectional"))
      (node (ref "U1") (pin "3") (pinfunction "D_3") (pintype "input"))
    )
    (net (code "57") (name "PROM_S") (class "Default")
      (node (ref "R8") (pin "1") (pinfunction "1_1") (pintype "passive"))
      (node (ref "U$3") (pin "P72") (pinfunction "IO_L06P_1_P72") (pintype "bidirectional"))
      (node (ref "U1") (pin "1") (pinfunction "S_1") (pintype "input"))
    )
    (net (code "58") (name "REF3V") (class "Default")
      (node (ref "C6") (pin "1") (pinfunction "1_1") (pintype "passive"))
      (node (ref "C7") (pin "1") (pinfunction "1_1") (pintype "passive"))
      (node (ref "U$2") (pin "P$7") (pinfunction "REF1_P$7") (pintype "bidirectional"))
      (node (ref "U$2") (pin "P$8") (pinfunction "REF2_P$8") (pintype "bidirectional"))
      (node (ref "U6") (pin "5") (pinfunction "VOUT_SENSE_5") (pintype "output"))
      (node (ref "U6") (pin "6") (pinfunction "VOUT_FORCE_6") (pintype "output"))
    )
    (net (code "59") (name "SCK") (class "Default")
      (node (ref "U$2") (pin "P$13") (pinfunction "SCK_P$13") (pintype "bidirectional"))
      (node (ref "U$3") (pin "P4") (pinfunction "IO_L01N_3_P4") (pintype "bidirectional"))
    )
    (net (code "60") (name "SDO") (class "Default")
      (node (ref "U$2") (pin "P$14") (pinfunction "SDO_P$14") (pintype "bidirectional"))
      (node (ref "U$3") (pin "P3") (pinfunction "IO_L01P_3_P3") (pintype "bidirectional"))
    )
    (net (code "61") (name "SH") (class "Default")
      (node (ref "U$1") (pin "P$5") (pinfunction "SH_P$5") (pintype "bidirectional"))
      (node (ref "U$3") (pin "P16") (pinfunction "IO_L05N_3/LHCLK7_P16") (pintype "bidirectional"))
    )
    (net (code "62") (name "TCK") (class "Default")
      (node (ref "TCK") (pin "P$1") (pinfunction "P$1_P$1") (pintype "bidirectional"))
      (node (ref "U$3") (pin "P76") (pinfunction "TCK_P76") (pintype "bidirectional"))
      (node (ref "U8") (pin "6") (pinfunction "TCK_6") (pintype "input"))
    )
    (net (code "63") (name "TDII") (class "Default")
      (node (ref "U$3") (pin "P75") (pinfunction "TDO_P75") (pintype "bidirectional"))
      (node (ref "U8") (pin "4") (pinfunction "TDI_4") (pintype "input"))
    )
    (net (code "64") (name "TDO") (class "Default")
      (node (ref "TDO") (pin "P$1") (pinfunction "P$1_P$1") (pintype "bidirectional"))
      (node (ref "U8") (pin "17") (pinfunction "TDO_17") (pintype "output"))
    )
    (net (code "65") (name "TMS") (class "Default")
      (node (ref "TMS") (pin "P$1") (pinfunction "P$1_P$1") (pintype "bidirectional"))
      (node (ref "U$3") (pin "P1") (pinfunction "TMS_P1") (pintype "bidirectional"))
      (node (ref "U8") (pin "5") (pinfunction "TMS_5") (pintype "input"))
    )
    (net (code "66") (name "VCC5") (class "Default")
      (node (ref "C1") (pin "1") (pinfunction "1_1") (pintype "passive"))
      (node (ref "C17") (pin "1") (pinfunction "1_1") (pintype "passive"))
      (node (ref "C21") (pin "1") (pinfunction "1_1") (pintype "passive"))
      (node (ref "C30") (pin "1") (pinfunction "1_1") (pintype "passive"))
      (node (ref "U$1") (pin "P$1") (pinfunction "VDD_P$1") (pintype "bidirectional"))
      (node (ref "U$1") (pin "P$2") (pinfunction "VAD_P$2") (pintype "bidirectional"))
      (node (ref "U3") (pin "3") (pinfunction "IN_3") (pintype "input"))
      (node (ref "U4") (pin "3") (pinfunction "IN_3") (pintype "input"))
      (node (ref "U9") (pin "3") (pinfunction "IN_3") (pintype "input"))
      (node (ref "X1") (pin "1") (pinfunction "1_1") (pintype "passive"))
    )
    (net (code "67") (name "VCC12") (class "Default")
      (node (ref "C29") (pin "1") (pinfunction "1_1") (pintype "passive"))
      (node (ref "C61") (pin "1") (pinfunction "1_1") (pintype "passive"))
      (node (ref "C62") (pin "1") (pinfunction "1_1") (pintype "passive"))
      (node (ref "C63") (pin "1") (pinfunction "1_1") (pintype "passive"))
      (node (ref "C64") (pin "1") (pinfunction "1_1") (pintype "passive"))
      (node (ref "R9") (pin "1") (pinfunction "1_1") (pintype "passive"))
      (node (ref "U$3") (pin "P17") (pinfunction "VCCINT_P17") (pintype "bidirectional"))
      (node (ref "U$3") (pin "P38") (pinfunction "VCCINT_P38") (pintype "bidirectional"))
      (node (ref "U$3") (pin "P66") (pinfunction "VCCINT_P66") (pintype "bidirectional"))
      (node (ref "U$3") (pin "P81") (pinfunction "VCCINT_P81") (pintype "bidirectional"))
      (node (ref "U9") (pin "2") (pinfunction "OUT_2") (pintype "output"))
      (node (ref "U9") (pin "4") (pinfunction "OUT_4") (pintype "output"))
    )
    (net (code "68") (name "VCC18") (class "Default")
      (node (ref "C10") (pin "1") (pinfunction "1_1") (pintype "passive"))
      (node (ref "C11") (pin "1") (pinfunction "1_1") (pintype "passive"))
      (node (ref "C14") (pin "1") (pinfunction "1_1") (pintype "passive"))
      (node (ref "IC2") (pin "12") (pinfunction "VCORE0_12") (pintype "bidirectional"))
      (node (ref "IC2") (pin "37") (pinfunction "VCORE1_37") (pintype "bidirectional"))
      (node (ref "IC2") (pin "49") (pinfunction "VREGOUT_49") (pintype "bidirectional"))
      (node (ref "IC2") (pin "64") (pinfunction "VCORE2_64") (pintype "bidirectional"))
    )
    (net (code "69") (name "VCC25") (class "Default")
      (node (ref "C18") (pin "1") (pinfunction "1_1") (pintype "passive"))
      (node (ref "C8") (pin "1") (pinfunction "1_1") (pintype "passive"))
      (node (ref "U$2") (pin "P$2") (pinfunction "VDD_P$2") (pintype "bidirectional"))
      (node (ref "U4") (pin "2") (pinfunction "OUT_2") (pintype "output"))
      (node (ref "U4") (pin "4") (pinfunction "OUT_4") (pintype "output"))
    )
    (net (code "70") (name "VCC33") (class "Default")
      (node (ref "3.3V") (pin "P$1") (pinfunction "P$1_P$1") (pintype "bidirectional"))
      (node (ref "C12") (pin "1") (pinfunction "1_1") (pintype "passive"))
      (node (ref "C13") (pin "1") (pinfunction "1_1") (pintype "passive"))
      (node (ref "C15") (pin "1") (pinfunction "1_1") (pintype "passive"))
      (node (ref "C16") (pin "1") (pinfunction "1_1") (pintype "passive"))
      (node (ref "C19") (pin "1") (pinfunction "1_1") (pintype "passive"))
      (node (ref "C2") (pin "1") (pinfunction "1_1") (pintype "passive"))
      (node (ref "C20") (pin "1") (pinfunction "1_1") (pintype "passive"))
      (node (ref "C22") (pin "1") (pinfunction "1_1") (pintype "passive"))
      (node (ref "C27") (pin "1") (pinfunction "1_1") (pintype "passive"))
      (node (ref "C4") (pin "1") (pinfunction "1_1") (pintype "passive"))
      (node (ref "C5") (pin "1") (pinfunction "1_1") (pintype "passive"))
      (node (ref "C59") (pin "1") (pinfunction "1_1") (pintype "passive"))
      (node (ref "C60") (pin "1") (pinfunction "1_1") (pintype "passive"))
      (node (ref "C70") (pin "1") (pinfunction "1_1") (pintype "passive"))
      (node (ref "C72") (pin "1") (pinfunction "1_1") (pintype "passive"))
      (node (ref "C73") (pin "1") (pinfunction "1_1") (pintype "passive"))
      (node (ref "C74") (pin "1") (pinfunction "1_1") (pintype "passive"))
      (node (ref "C76") (pin "1") (pinfunction "1_1") (pintype "passive"))
      (node (ref "C78") (pin "1") (pinfunction "1_1") (pintype "passive"))
      (node (ref "C81") (pin "1") (pinfunction "1_1") (pintype "passive"))
      (node (ref "C9") (pin "1") (pinfunction "1_1") (pintype "passive"))
      (node (ref "IC2") (pin "20") (pinfunction "VCCIO0_20") (pintype "bidirectional"))
      (node (ref "IC2") (pin "31") (pinfunction "VCCIO1_31") (pintype "bidirectional"))
      (node (ref "IC2") (pin "42") (pinfunction "VCCIO2_42") (pintype "bidirectional"))
      (node (ref "IC2") (pin "50") (pinfunction "VREGIN_50") (pintype "bidirectional"))
      (node (ref "IC2") (pin "56") (pinfunction "VCCIO3_56") (pintype "bidirectional"))
      (node (ref "L3") (pin "2") (pinfunction "2_2") (pintype "passive"))
      (node (ref "L4") (pin "2") (pinfunction "2_2") (pintype "passive"))
      (node (ref "Q1") (pin "4") (pinfunction "VCC_4") (pintype "power_in"))
      (node (ref "Q2") (pin "4") (pinfunction "VCC_4") (pintype "power_in"))
      (node (ref "R10") (pin "2") (pinfunction "2_2") (pintype "passive"))
      (node (ref "R2") (pin "2") (pinfunction "2_2") (pintype "passive"))
      (node (ref "R3") (pin "2") (pinfunction "2_2") (pintype "passive"))
      (node (ref "R4") (pin "2") (pinfunction "2_2") (pintype "passive"))
      (node (ref "R5") (pin "2") (pinfunction "2_2") (pintype "passive"))
      (node (ref "R7") (pin "2") (pinfunction "2_2") (pintype "passive"))
      (node (ref "R8") (pin "2") (pinfunction "2_2") (pintype "passive"))
      (node (ref "U$2") (pin "P$15") (pinfunction "OVDD_P$15") (pintype "bidirectional"))
      (node (ref "U$3") (pin "P11") (pinfunction "VCCO_3_P11") (pintype "bidirectional"))
      (node (ref "U$3") (pin "P22") (pinfunction "VCCAUX_P22") (pintype "bidirectional"))
      (node (ref "U$3") (pin "P26") (pinfunction "VCCO_2_P26") (pintype "bidirectional"))
      (node (ref "U$3") (pin "P45") (pinfunction "VCCO_2_P45") (pintype "bidirectional"))
      (node (ref "U$3") (pin "P55") (pinfunction "VCCAUX_P55") (pintype "bidirectional"))
      (node (ref "U$3") (pin "P67") (pinfunction "VCCO_1_P67") (pintype "bidirectional"))
      (node (ref "U$3") (pin "P79") (pinfunction "VCCO_0_P79") (pintype "bidirectional"))
      (node (ref "U$3") (pin "P92") (pinfunction "VCCAUX_P92") (pintype "bidirectional"))
      (node (ref "U$3") (pin "P96") (pinfunction "VCCO_0_P96") (pintype "bidirectional"))
      (node (ref "U1") (pin "6") (pinfunction "ORG_6") (pintype "input"))
      (node (ref "U1") (pin "8") (pinfunction "VCC_8") (pintype "power_in"))
      (node (ref "U2") (pin "5") (pinfunction "V+_5") (pintype "power_in"))
      (node (ref "U3") (pin "2") (pinfunction "OUT_2") (pintype "output"))
      (node (ref "U3") (pin "4") (pinfunction "OUT_4") (pintype "output"))
      (node (ref "U6") (pin "3") (pinfunction "ENABLE_3") (pintype "input"))
      (node (ref "U6") (pin "4") (pinfunction "VIN_4") (pintype "input"))
      (node (ref "U7") (pin "6") (pinfunction "ORG_6") (pintype "input"))
      (node (ref "U7") (pin "8") (pinfunction "VCC_8") (pintype "power_in"))
      (node (ref "U8") (pin "18") (pinfunction "VCCINT_18") (pintype "power_in"))
      (node (ref "U8") (pin "19") (pinfunction "VCCO_19") (pintype "power_in"))
      (node (ref "U8") (pin "20") (pinfunction "VCCJ_20") (pintype "power_in"))
    )
    (net (code "71") (name "unconnected-(IC2-ACBUS4{slash}TXLED#{slash}GPIOH4-Pad30)") (class "Default")
      (node (ref "IC2") (pin "30") (pinfunction "ACBUS4/TXLED#/GPIOH4_30") (pintype "bidirectional"))
    )
    (net (code "72") (name "unconnected-(IC2-ACBUS7{slash}GPIOH7-Pad34)") (class "Default")
      (node (ref "IC2") (pin "34") (pinfunction "ACBUS7/GPIOH7_34") (pintype "bidirectional"))
    )
    (net (code "73") (name "unconnected-(IC2-BCBUS0{slash}GPIOH1-Pad48)") (class "Default")
      (node (ref "IC2") (pin "48") (pinfunction "BCBUS0/GPIOH1_48") (pintype "bidirectional"))
    )
    (net (code "74") (name "unconnected-(IC2-BCBUS1{slash}GPIOH2-Pad52)") (class "Default")
      (node (ref "IC2") (pin "52") (pinfunction "BCBUS1/GPIOH2_52") (pintype "bidirectional"))
    )
    (net (code "75") (name "unconnected-(IC2-BCBUS2-Pad53)") (class "Default")
      (node (ref "IC2") (pin "53") (pinfunction "BCBUS2_53") (pintype "bidirectional"))
    )
    (net (code "76") (name "unconnected-(IC2-BCBUS3{slash}RXLED#{slash}GPIOH3-Pad54)") (class "Default")
      (node (ref "IC2") (pin "54") (pinfunction "BCBUS3/RXLED#/GPIOH3_54") (pintype "bidirectional"))
    )
    (net (code "77") (name "unconnected-(IC2-BCBUS4{slash}TXLED#{slash}GPIOH4-Pad55)") (class "Default")
      (node (ref "IC2") (pin "55") (pinfunction "BCBUS4/TXLED#/GPIOH4_55") (pintype "bidirectional"))
    )
    (net (code "78") (name "unconnected-(IC2-BCBUS5{slash}GPIOH5-Pad57)") (class "Default")
      (node (ref "IC2") (pin "57") (pinfunction "BCBUS5/GPIOH5_57") (pintype "bidirectional"))
    )
    (net (code "79") (name "unconnected-(IC2-BCBUS6{slash}GPIOH6-Pad58)") (class "Default")
      (node (ref "IC2") (pin "58") (pinfunction "BCBUS6/GPIOH6_58") (pintype "bidirectional"))
    )
    (net (code "80") (name "unconnected-(IC2-BCBUS7{slash}GPIOH7-Pad59)") (class "Default")
      (node (ref "IC2") (pin "59") (pinfunction "BCBUS7/GPIOH7_59") (pintype "bidirectional"))
    )
    (net (code "81") (name "unconnected-(IC2-BDBUS4{slash}DTR#{slash}GPIOL0-Pad43)") (class "Default")
      (node (ref "IC2") (pin "43") (pinfunction "BDBUS4/DTR#/GPIOL0_43") (pintype "bidirectional"))
    )
    (net (code "82") (name "unconnected-(IC2-BDBUS5{slash}DSR#{slash}GPIOL1-Pad44)") (class "Default")
      (node (ref "IC2") (pin "44") (pinfunction "BDBUS5/DSR#/GPIOL1_44") (pintype "bidirectional"))
    )
    (net (code "83") (name "unconnected-(IC2-BDBUS6{slash}DCD#{slash}GPIOL2-Pad45)") (class "Default")
      (node (ref "IC2") (pin "45") (pinfunction "BDBUS6/DCD#/GPIOL2_45") (pintype "bidirectional"))
    )
    (net (code "84") (name "unconnected-(IC2-BDBUS7{slash}RI#{slash}GPIOL3-Pad46)") (class "Default")
      (node (ref "IC2") (pin "46") (pinfunction "BDBUS7/RI#/GPIOL3_46") (pintype "bidirectional"))
    )
    (net (code "85") (name "unconnected-(IC2-OSC0-Pad3)") (class "Default")
      (node (ref "IC2") (pin "3") (pinfunction "OSC0_3") (pintype "bidirectional"))
    )
    (net (code "86") (name "unconnected-(IC2-PWREN#-Pad60)") (class "Default")
      (node (ref "IC2") (pin "60") (pinfunction "PWREN#_60") (pintype "bidirectional"))
    )
    (net (code "87") (name "unconnected-(IC2-SUSPEND#-Pad36)") (class "Default")
      (node (ref "IC2") (pin "36") (pinfunction "SUSPEND#_36") (pintype "bidirectional"))
    )
    (net (code "88") (name "unconnected-(Q1-OE-Pad1)") (class "Default")
      (node (ref "Q1") (pin "1") (pinfunction "OE_1") (pintype "input"))
    )
    (net (code "89") (name "unconnected-(Q2-OE-Pad1)") (class "Default")
      (node (ref "Q2") (pin "1") (pinfunction "OE_1") (pintype "input"))
    )
    (net (code "90") (name "unconnected-(SV2-Pad13)") (class "Default")
      (node (ref "SV2") (pin "13") (pinfunction "13_13") (pintype "passive"))
    )
    (net (code "91") (name "unconnected-(SV2-Pad15)") (class "Default")
      (node (ref "SV2") (pin "15") (pinfunction "15_15") (pintype "passive"))
    )
    (net (code "92") (name "unconnected-(U$3A-IO_L01N_0-PadP78)") (class "Default")
      (node (ref "U$3") (pin "P78") (pinfunction "IO_L01N_0_P78") (pintype "bidirectional"))
    )
    (net (code "93") (name "unconnected-(U$3A-IO_L01P_0{slash}VREF_0-PadP77)") (class "Default")
      (node (ref "U$3") (pin "P77") (pinfunction "IO_L01P_0/VREF_0_P77") (pintype "bidirectional"))
    )
    (net (code "94") (name "unconnected-(U$3A-IO_L02N_0{slash}GCLK5-PadP84)") (class "Default")
      (node (ref "U$3") (pin "P84") (pinfunction "IO_L02N_0/GCLK5_P84") (pintype "bidirectional"))
    )
    (net (code "95") (name "unconnected-(U$3A-IO_L03P_0{slash}GCLK6-PadP85)") (class "Default")
      (node (ref "U$3") (pin "P85") (pinfunction "IO_L03P_0/GCLK6_P85") (pintype "bidirectional"))
    )
    (net (code "96") (name "unconnected-(U$3A-IO_L05N_0-PadP94)") (class "Default")
      (node (ref "U$3") (pin "P94") (pinfunction "IO_L05N_0_P94") (pintype "bidirectional"))
    )
    (net (code "97") (name "unconnected-(U$3A-IO_L05P_0-PadP93)") (class "Default")
      (node (ref "U$3") (pin "P93") (pinfunction "IO_L05P_0_P93") (pintype "bidirectional"))
    )
    (net (code "98") (name "unconnected-(U$3A-IO_L06P_0{slash}VREF_0-PadP98)") (class "Default")
      (node (ref "U$3") (pin "P98") (pinfunction "IO_L06P_0/VREF_0_P98") (pintype "bidirectional"))
    )
    (net (code "99") (name "unconnected-(U$3A-IP_0-PadP97)") (class "Default")
      (node (ref "U$3") (pin "P97") (pinfunction "IP_0_P97") (pintype "bidirectional"))
    )
    (net (code "100") (name "unconnected-(U$3A-IP_0{slash}VREF_0-PadP82)") (class "Default")
      (node (ref "U$3") (pin "P82") (pinfunction "IP_0/VREF_0_P82") (pintype "bidirectional"))
    )
    (net (code "101") (name "unconnected-(U$3B-IO_L01N_1-PadP57)") (class "Default")
      (node (ref "U$3") (pin "P57") (pinfunction "IO_L01N_1_P57") (pintype "bidirectional"))
    )
    (net (code "102") (name "unconnected-(U$3B-IO_L01P_1-PadP56)") (class "Default")
      (node (ref "U$3") (pin "P56") (pinfunction "IO_L01P_1_P56") (pintype "bidirectional"))
    )
    (net (code "103") (name "unconnected-(U$3B-IO_L02N_1{slash}RHCLK1-PadP60)") (class "Default")
      (node (ref "U$3") (pin "P60") (pinfunction "IO_L02N_1/RHCLK1_P60") (pintype "bidirectional"))
    )
    (net (code "104") (name "unconnected-(U$3B-IO_L02P_1{slash}RHCLK0-PadP59)") (class "Default")
      (node (ref "U$3") (pin "P59") (pinfunction "IO_L02P_1/RHCLK0_P59") (pintype "bidirectional"))
    )
    (net (code "105") (name "unconnected-(U$3B-IO_L03N_1{slash}TRDY1{slash}RHCLK3-PadP62)") (class "Default")
      (node (ref "U$3") (pin "P62") (pinfunction "IO_L03N_1/TRDY1/RHCLK3_P62") (pintype "bidirectional"))
    )
    (net (code "106") (name "unconnected-(U$3B-IO_L03P_1{slash}RHCLK2-PadP61)") (class "Default")
      (node (ref "U$3") (pin "P61") (pinfunction "IO_L03P_1/RHCLK2_P61") (pintype "bidirectional"))
    )
    (net (code "107") (name "unconnected-(U$3B-IO_L04N_1{slash}RHCLK7-PadP65)") (class "Default")
      (node (ref "U$3") (pin "P65") (pinfunction "IO_L04N_1/RHCLK7_P65") (pintype "bidirectional"))
    )
    (net (code "108") (name "unconnected-(U$3B-IO_L04P_1{slash}IRDY1{slash}RHCLK6-PadP64)") (class "Default")
      (node (ref "U$3") (pin "P64") (pinfunction "IO_L04P_1/IRDY1/RHCLK6_P64") (pintype "bidirectional"))
    )
    (net (code "109") (name "unconnected-(U$3B-IO_L05N_1-PadP71)") (class "Default")
      (node (ref "U$3") (pin "P71") (pinfunction "IO_L05N_1_P71") (pintype "bidirectional"))
    )
    (net (code "110") (name "unconnected-(U$3B-IP_1{slash}VREF_1-PadP68)") (class "Default")
      (node (ref "U$3") (pin "P68") (pinfunction "IP_1/VREF_1_P68") (pintype "bidirectional"))
    )
    (net (code "111") (name "unconnected-(U$3C-IO_2{slash}MOSI{slash}CSI_B-PadP46)") (class "Default")
      (node (ref "U$3") (pin "P46") (pinfunction "IO_2/MOSI/CSI_B_P46") (pintype "bidirectional"))
    )
    (net (code "112") (name "unconnected-(U$3C-IO_L02N_2{slash}CSO_B-PadP27)") (class "Default")
      (node (ref "U$3") (pin "P27") (pinfunction "IO_L02N_2/CSO_B_P27") (pintype "bidirectional"))
    )
    (net (code "113") (name "unconnected-(U$3C-IO_L04P_2{slash}VS1-PadP30)") (class "Default")
      (node (ref "U$3") (pin "P30") (pinfunction "IO_L04P_2/VS1_P30") (pintype "bidirectional"))
    )
    (net (code "114") (name "unconnected-(U$3C-IO_L06P_2{slash}D7-PadP34)") (class "Default")
      (node (ref "U$3") (pin "P34") (pinfunction "IO_L06P_2/D7_P34") (pintype "bidirectional"))
    )
    (net (code "115") (name "unconnected-(U$3C-IO_L08N_2{slash}GCLK15-PadP41)") (class "Default")
      (node (ref "U$3") (pin "P41") (pinfunction "IO_L08N_2/GCLK15_P41") (pintype "bidirectional"))
    )
    (net (code "116") (name "unconnected-(U$3C-IO_L08P_2{slash}GCLK14-PadP40)") (class "Default")
      (node (ref "U$3") (pin "P40") (pinfunction "IO_L08P_2/GCLK14_P40") (pintype "bidirectional"))
    )
    (net (code "117") (name "unconnected-(U$3C-IO_L09N_2{slash}GCLK1-PadP44)") (class "Default")
      (node (ref "U$3") (pin "P44") (pinfunction "IO_L09N_2/GCLK1_P44") (pintype "bidirectional"))
    )
    (net (code "118") (name "unconnected-(U$3C-IO_L09P_2{slash}GCLK0-PadP43)") (class "Default")
      (node (ref "U$3") (pin "P43") (pinfunction "IO_L09P_2/GCLK0_P43") (pintype "bidirectional"))
    )
    (net (code "119") (name "unconnected-(U$3C-IO_L10N_2{slash}D3-PadP49)") (class "Default")
      (node (ref "U$3") (pin "P49") (pinfunction "IO_L10N_2/D3_P49") (pintype "bidirectional"))
    )
    (net (code "120") (name "unconnected-(U$3C-IO_L11N_2{slash}D1-PadP52)") (class "Default")
      (node (ref "U$3") (pin "P52") (pinfunction "IO_L11N_2/D1_P52") (pintype "bidirectional"))
    )
    (net (code "121") (name "unconnected-(U$3C-IO_L11P_2{slash}D2-PadP50)") (class "Default")
      (node (ref "U$3") (pin "P50") (pinfunction "IO_L11P_2/D2_P50") (pintype "bidirectional"))
    )
    (net (code "122") (name "unconnected-(U$3C-IP_2{slash}VREF_2-PadP39)") (class "Default")
      (node (ref "U$3") (pin "P39") (pinfunction "IP_2/VREF_2_P39") (pintype "bidirectional"))
    )
    (net (code "123") (name "unconnected-(U$3D-IO_L03N_3{slash}LHCLK1-PadP10)") (class "Default")
      (node (ref "U$3") (pin "P10") (pinfunction "IO_L03N_3/LHCLK1_P10") (pintype "bidirectional"))
    )
    (net (code "124") (name "unconnected-(U$3D-IO_L03P_3{slash}LHCLK0-PadP9)") (class "Default")
      (node (ref "U$3") (pin "P9") (pinfunction "IO_L03P_3/LHCLK0_P9") (pintype "bidirectional"))
    )
    (net (code "125") (name "unconnected-(U$3D-IO_L04P_3{slash}LHCLK2-PadP12)") (class "Default")
      (node (ref "U$3") (pin "P12") (pinfunction "IO_L04P_3/LHCLK2_P12") (pintype "bidirectional"))
    )
    (net (code "126") (name "unconnected-(U$3D-IO_L06N_3-PadP20)") (class "Default")
      (node (ref "U$3") (pin "P20") (pinfunction "IO_L06N_3_P20") (pintype "bidirectional"))
    )
    (net (code "127") (name "unconnected-(U$3D-IO_L06P_3-PadP19)") (class "Default")
      (node (ref "U$3") (pin "P19") (pinfunction "IO_L06P_3_P19") (pintype "bidirectional"))
    )
    (net (code "128") (name "unconnected-(U$3D-IP_3-PadP21)") (class "Default")
      (node (ref "U$3") (pin "P21") (pinfunction "IP_3_P21") (pintype "bidirectional"))
    )
    (net (code "129") (name "unconnected-(U$3D-IP_3{slash}VREF_3-PadP7)") (class "Default")
      (node (ref "U$3") (pin "P7") (pinfunction "IP_3/VREF_3_P7") (pintype "bidirectional"))
    )
    (net (code "130") (name "unconnected-(U8-(DNC)-Pad16)") (class "Default")
      (node (ref "U8") (pin "16") (pinfunction "(DNC)_16") (pintype "no_connect"))
    )
    (net (code "131") (name "unconnected-(U8-(DNC)_2-Pad12)") (class "Default")
      (node (ref "U8") (pin "12") (pinfunction "(DNC)_2_12") (pintype "no_connect"))
    )
    (net (code "132") (name "unconnected-(U8-(DNC)_3-Pad2)") (class "Default")
      (node (ref "U8") (pin "2") (pinfunction "(DNC)_3_2") (pintype "no_connect"))
    )
    (net (code "133") (name "unconnected-(U8-(DNC)_4-Pad15)") (class "Default")
      (node (ref "U8") (pin "15") (pinfunction "(DNC)_4_15") (pintype "no_connect"))
    )
    (net (code "134") (name "unconnected-(U8-(DNC)_5-Pad9)") (class "Default")
      (node (ref "U8") (pin "9") (pinfunction "(DNC)_5_9") (pintype "no_connect"))
    )
    (net (code "135") (name "unconnected-(U8-(DNC)_6-Pad14)") (class "Default")
      (node (ref "U8") (pin "14") (pinfunction "(DNC)_6_14") (pintype "no_connect"))
    )
    (net (code "136") (name "unconnected-(U8-~{CEO}-Pad13)") (class "Default")
      (node (ref "U8") (pin "13") (pinfunction "~{CEO}_13") (pintype "output"))
    )
  )
)
